# EEZ_CF-DIC_r3B3.net
KiCad netlist of a schematic drawn in EAGLE
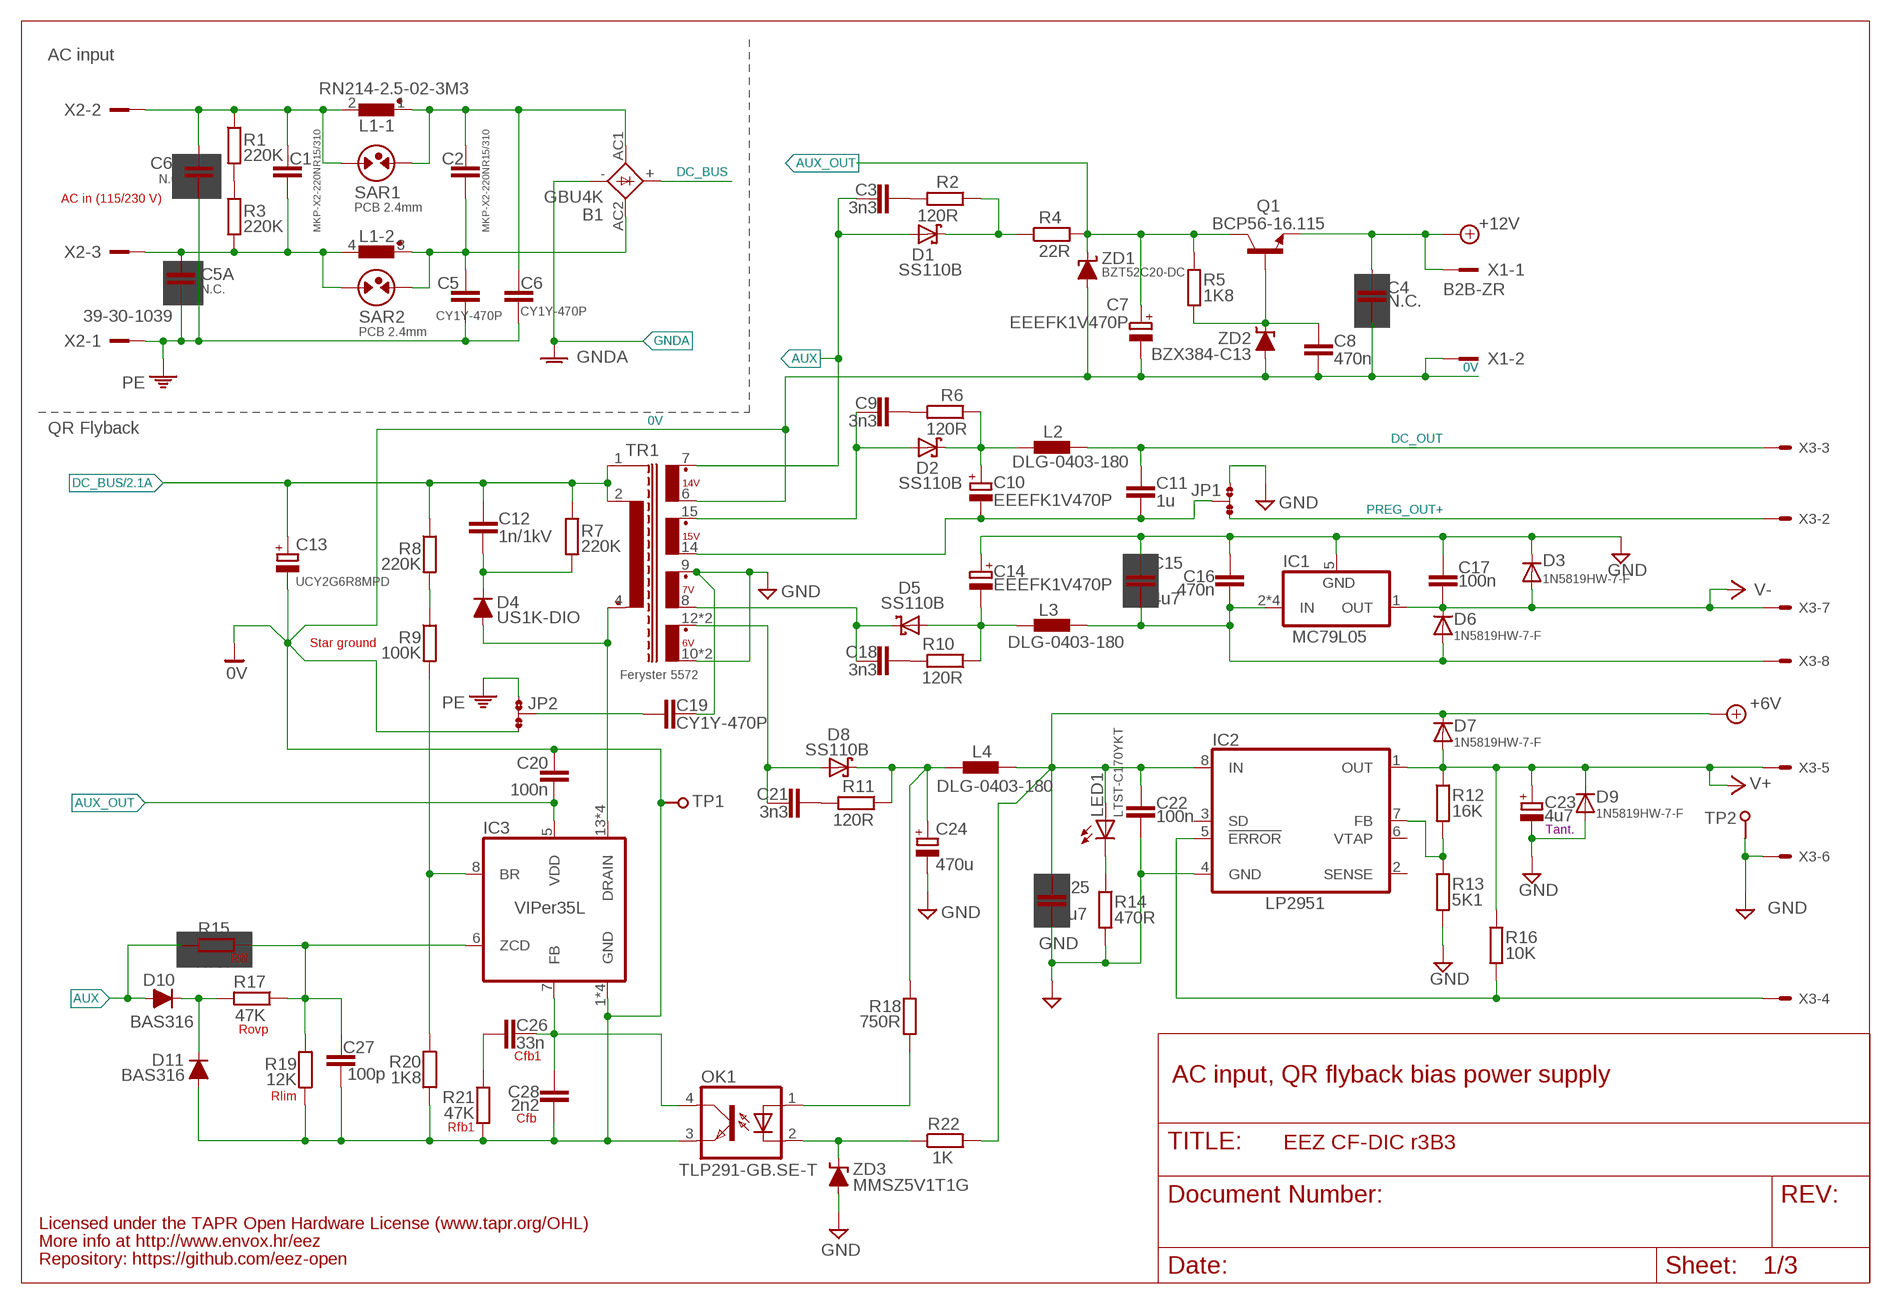
[diagram p0: schematic, sheet 1]
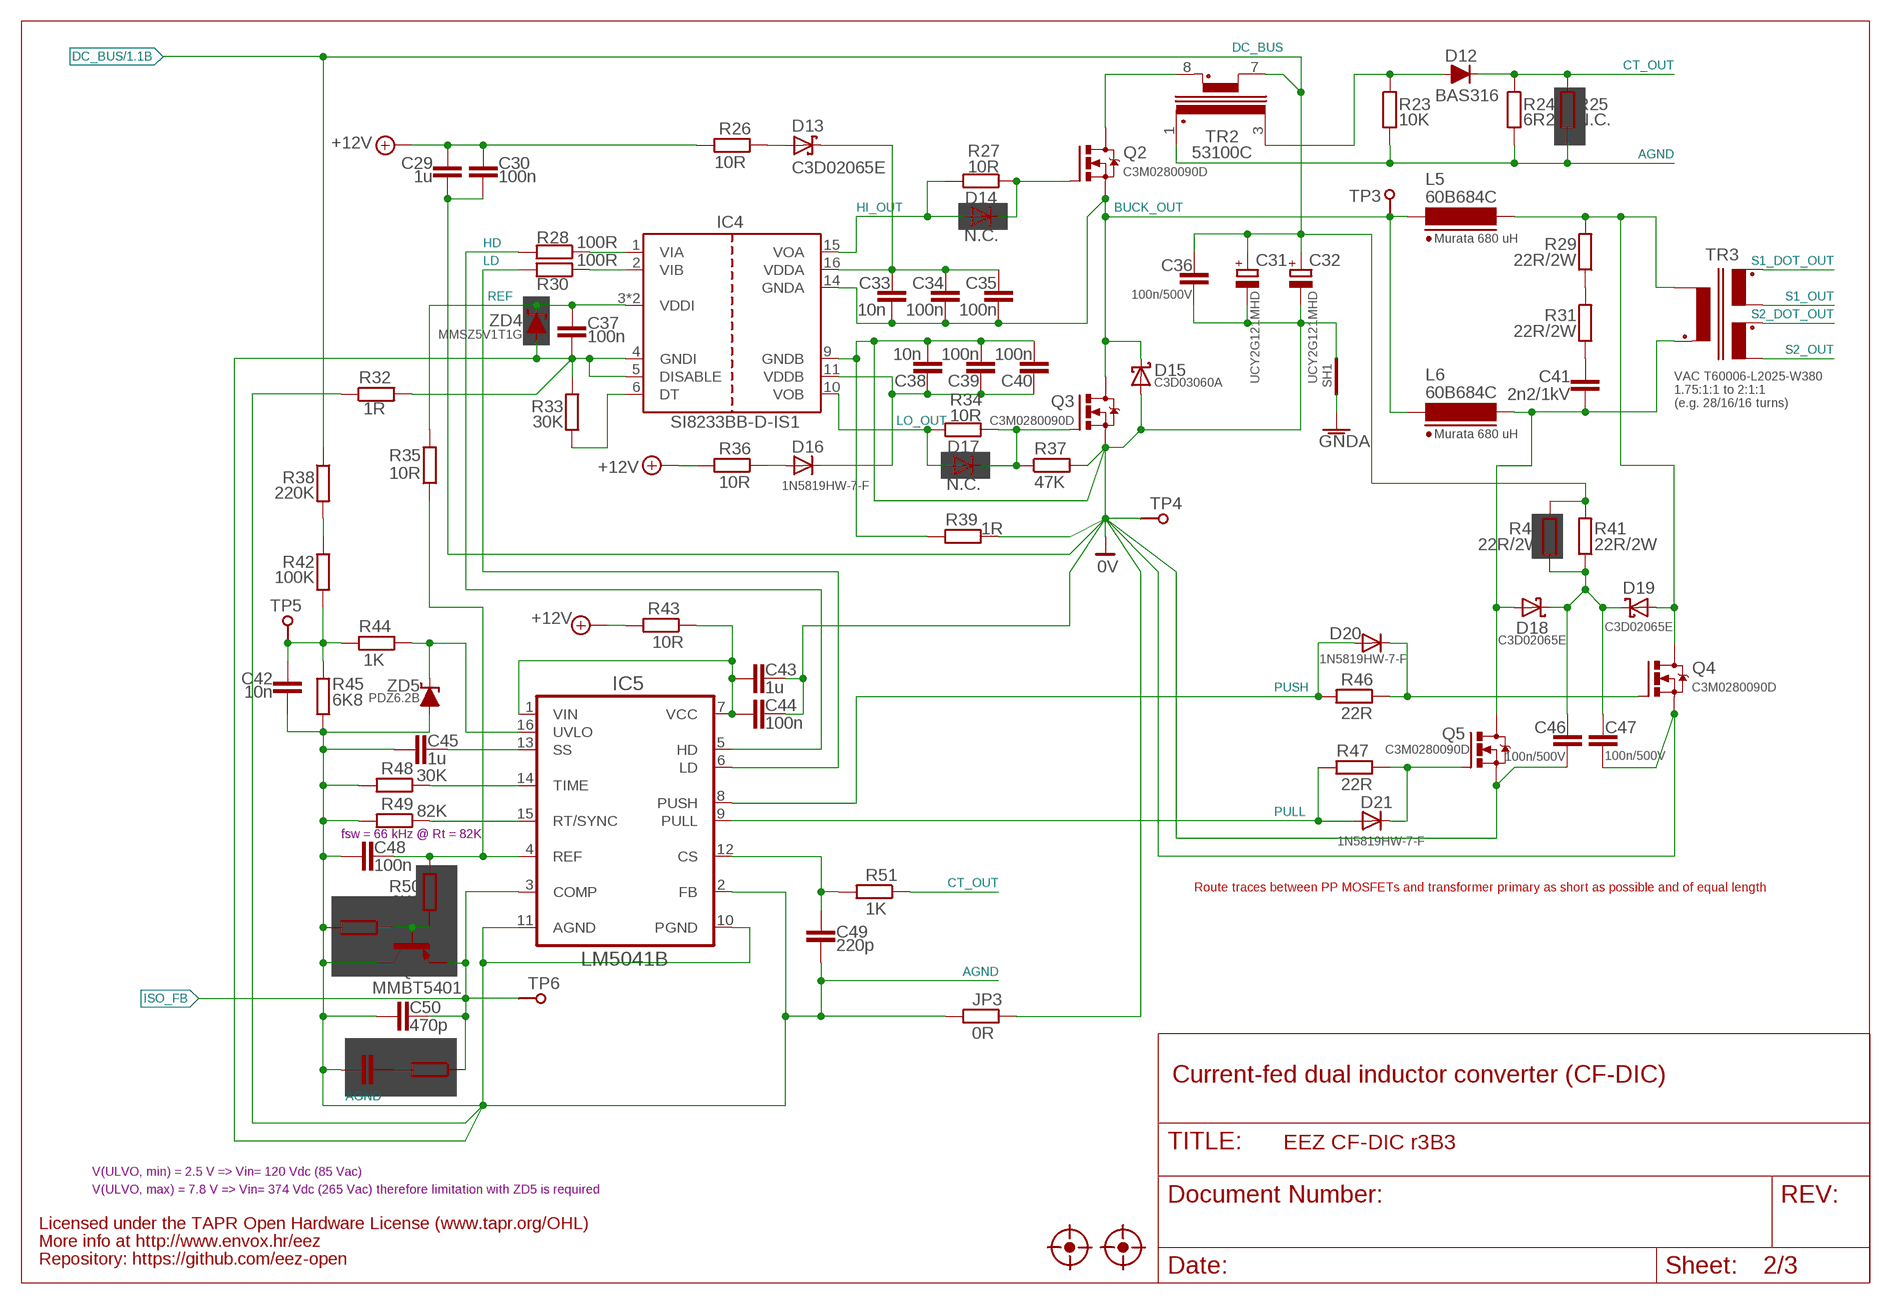
[diagram p1: schematic, sheet 2]
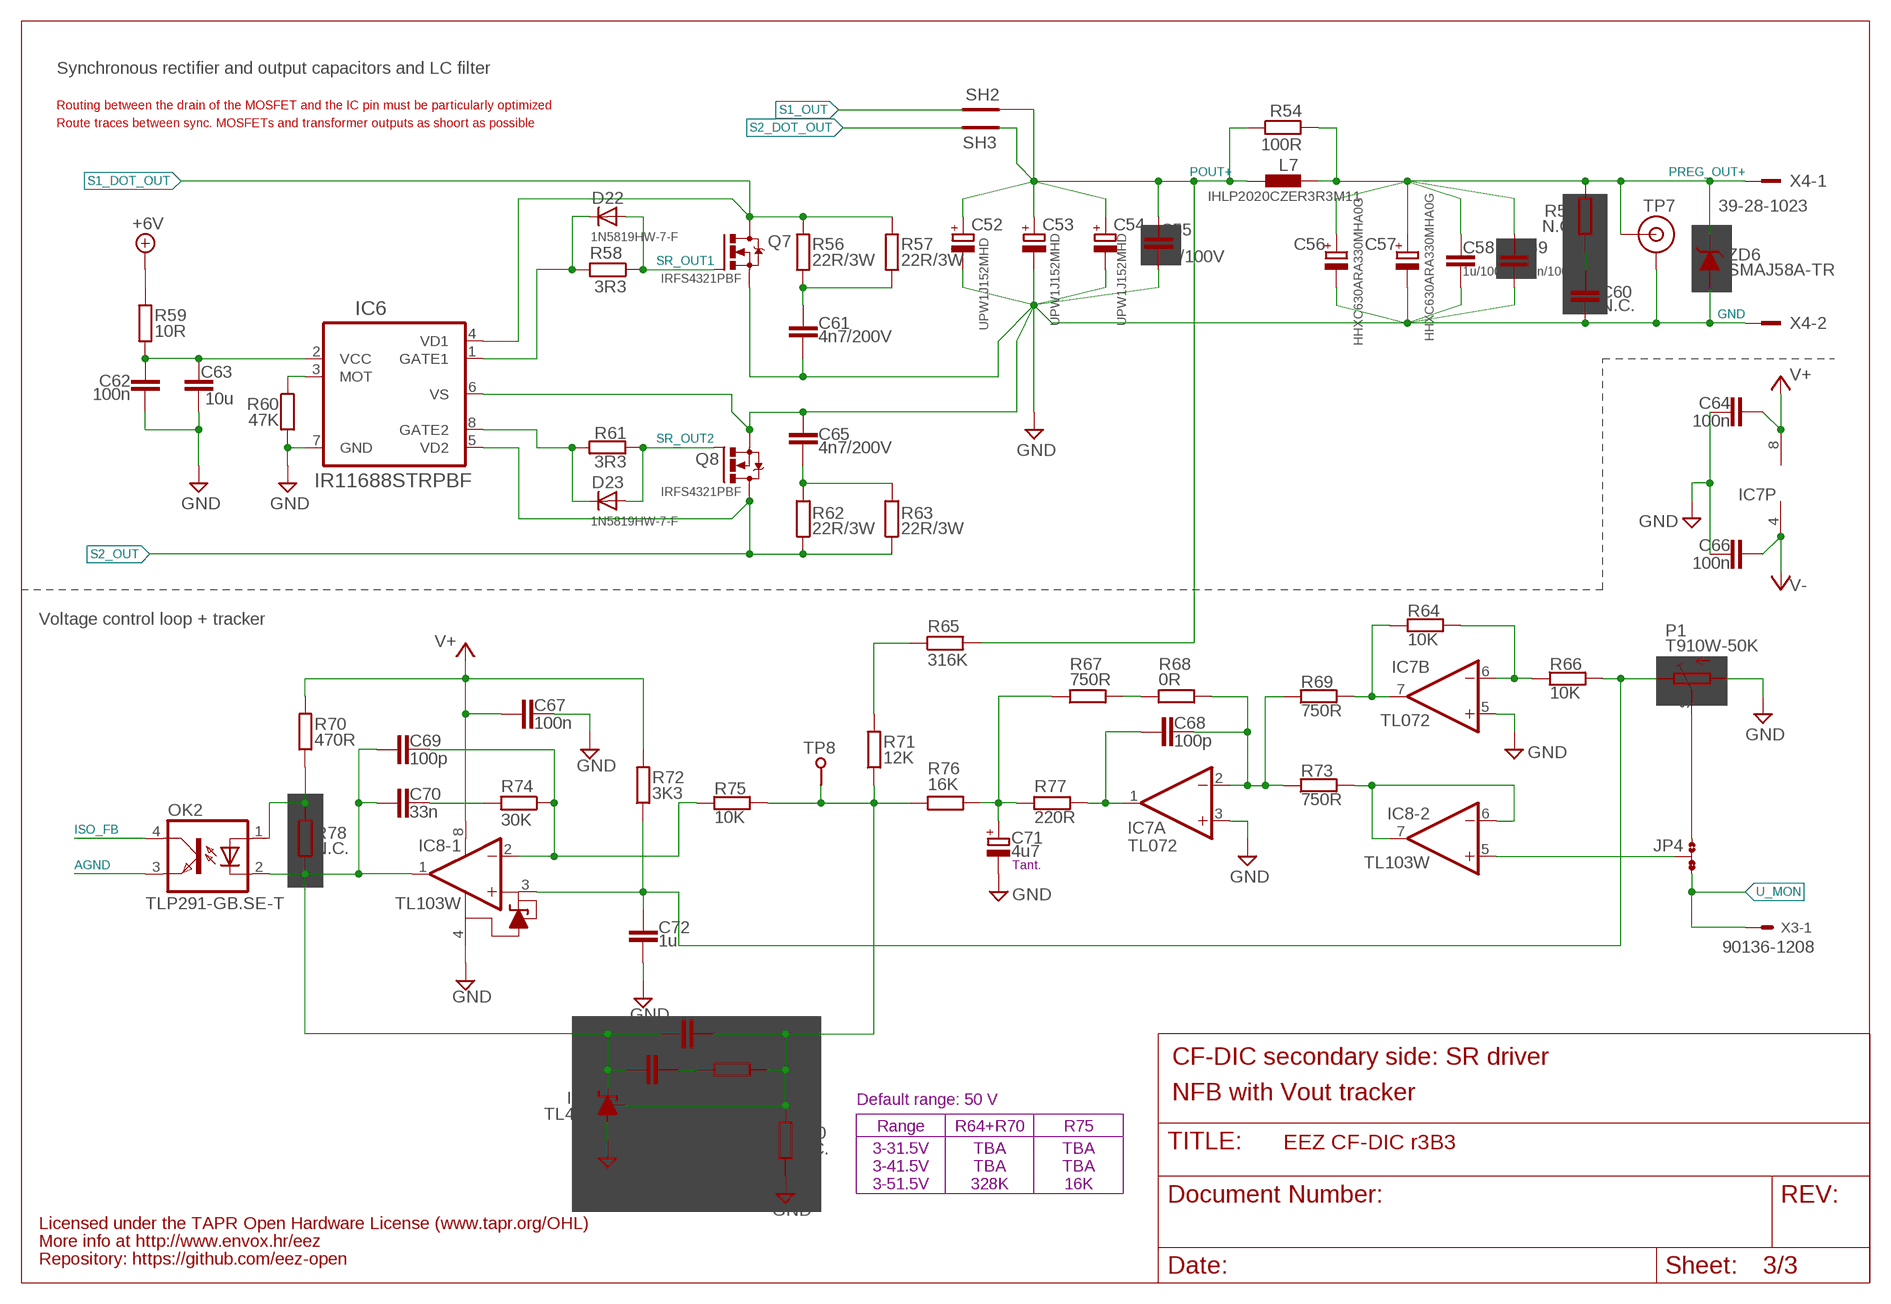
[diagram p2: schematic, sheet 3]

(export (version "E")
  (design (tool "Eeschema 10.0.6"))
  (components
    (comp (ref "C52")
      (value "UPW1J152MHD")
      (footprint "eagle-import:ECAP7.5_18")
      (libsource (lib "eagle-import") (part "ECAP7.5G_18MM"))
    )
    (comp (ref "C53")
      (value "UPW1J152MHD")
      (footprint "eagle-import:ECAP7.5_18")
      (libsource (lib "eagle-import") (part "ECAP7.5G_18MM"))
    )
    (comp (ref "C54")
      (value "UPW1J152MHD")
      (footprint "eagle-import:ECAP7.5_18")
      (libsource (lib "eagle-import") (part "ECAP7.5G_18MM"))
    )
    (comp (ref "C55")
      (value "1u/100V")
      (footprint "eagle-import:C1206")
      (libsource (lib "eagle-import") (part "C-EUC1206"))
    )
    (comp (ref "C56")
      (value "HHXC630ARA330MHA0G ")
      (footprint "eagle-import:CAPAE830X1050N")
      (fields
        (field (name "MPN") "EEE-FK1J470P")
        (field (name "TOLERANCE") "±20 %")
        (field (name "MPN_1") "EEE-FK1J470P")
        (field (name "OC_FARNELL") "9696032  ")
        (field (name "OC_NEWARK") "96K9403")
        (field (name "PACKAGE") "CASE-F")
        (field (name "SUPPLIER") "PANASONIC")
        (field (name "TOLERANCE_1") "±20 %")
        (field (name "VOLTAGERATING") "63 V")
      )
      (libsource (lib "eagle-import") (part "EEE--CASE-FFK1J470P"))
    )
    (comp (ref "C57")
      (value "HHXC630ARA330MHA0G")
      (footprint "eagle-import:CAPAE830X1050N")
      (fields (field (name "MPN") "EEE-FK1J470P") (field (name "TOLERANCE") "±20 %"))
      (libsource (lib "eagle-import") (part "EEE--CASE-FFK1J470P"))
    )
    (comp (ref "C58")
      (value "1u/100V")
      (footprint "eagle-import:C1206")
      (libsource (lib "eagle-import") (part "C-EUC1206"))
    )
    (comp (ref "C59")
      (value "100n/100V")
      (footprint "eagle-import:C0805")
      (libsource (lib "eagle-import") (part "C-EUC0805"))
    )
    (comp (ref "C60")
      (value "N.C.")
      (footprint "eagle-import:C1206")
      (libsource (lib "eagle-import") (part "C-EUC1206"))
    )
    (comp (ref "C61")
      (value "4n7/200V")
      (footprint "eagle-import:C1206")
      (libsource (lib "eagle-import") (part "C-EUC1206"))
    )
    (comp (ref "C62")
      (value "100n")
      (footprint "eagle-import:C0603")
      (libsource (lib "eagle-import") (part "C-EUC0603"))
    )
    (comp (ref "C63")
      (value "10u")
      (footprint "eagle-import:C1210")
      (libsource (lib "eagle-import") (part "C-EUC1210"))
    )
    (comp (ref "C64")
      (value "100n")
      (footprint "eagle-import:C0603")
      (libsource (lib "eagle-import") (part "C-EUC0603"))
    )
    (comp (ref "C65")
      (value "4n7/200V")
      (footprint "eagle-import:C1206")
      (libsource (lib "eagle-import") (part "C-EUC1206"))
    )
    (comp (ref "C66")
      (value "100n")
      (footprint "eagle-import:C0603")
      (libsource (lib "eagle-import") (part "C-EUC0603"))
    )
    (comp (ref "C67")
      (value "100n")
      (footprint "eagle-import:C0603")
      (libsource (lib "eagle-import") (part "C-EUC0603"))
    )
    (comp (ref "C68")
      (value "100p")
      (footprint "eagle-import:C0805")
      (libsource (lib "eagle-import") (part "C-EUC0805"))
    )
    (comp (ref "C69")
      (value "100p")
      (footprint "eagle-import:C0805")
      (libsource (lib "eagle-import") (part "C-EUC0805"))
    )
    (comp (ref "C70")
      (value "33n")
      (footprint "eagle-import:C0805")
      (libsource (lib "eagle-import") (part "C-EUC0805"))
    )
    (comp (ref "C71")
      (value "4u7")
      (footprint "eagle-import:EC1206")
      (libsource (lib "eagle-import") (part "ECAP1206"))
    )
    (comp (ref "C72")
      (value "1u")
      (footprint "eagle-import:C0805")
      (libsource (lib "eagle-import") (part "C-EUC0805"))
    )
    (comp (ref "C73")
      (value "N.C.")
      (footprint "eagle-import:C0805")
      (libsource (lib "eagle-import") (part "C-EUC0805"))
    )
    (comp (ref "C74")
      (value "N.C.")
      (footprint "eagle-import:C0805")
      (libsource (lib "eagle-import") (part "C-EUC0805"))
    )
    (comp (ref "D22")
      (value "1N5819HW-7-F")
      (footprint "eagle-import:SOD323-W")
      (libsource (lib "eagle-import") (part "DIODE-SOD323-W"))
    )
    (comp (ref "D23")
      (value "1N5819HW-7-F")
      (footprint "eagle-import:SOD323-W")
      (libsource (lib "eagle-import") (part "DIODE-SOD323-W"))
    )
    (comp (ref "IC6")
      (value "IR11688STRPBF")
      (footprint "eagle-import:SO8")
      (libsource (lib "eagle-import") (part "IR11688"))
    )
    (comp (ref "IC7")
      (value "TL072")
      (footprint "eagle-import:SOIC127P600X173-8N")
      (libsource (lib "eagle-import") (part "TL072SOIC8"))
    )
    (comp (ref "IC8")
      (value "TL103W")
      (footprint "eagle-import:SOIC127P600X173-8N")
      (libsource (lib "eagle-import") (part "TL103W"))
    )
    (comp (ref "IC9")
      (value "TL431")
      (footprint "eagle-import:SOT103P240X110-3N")
      (libsource (lib "eagle-import") (part "TL431"))
    )
    (comp (ref "JP4")
      (value "JP3-CUT")
      (footprint "eagle-import:JP3-CUT")
      (libsource (lib "eagle-import") (part "JP3-CUT"))
    )
    (comp (ref "L7")
      (value "IHLP2020CZER3R3M11")
      (footprint "eagle-import:IHLP-2020BZ-11")
      (libsource (lib "eagle-import") (part "EEZ_inductors_and_transformers_IHLP-2020BZ-11"))
    )
    (comp (ref "OK2")
      (value "TLP291-GB.SE-T")
      (footprint "eagle-import:SO4")
      (libsource (lib "eagle-import") (part "TLP291"))
    )
    (comp (ref "P1")
      (value "T910W-50K")
      (footprint "eagle-import:S64W")
      (libsource (lib "eagle-import") (part "TRIM_EU-S64W"))
    )
    (comp (ref "Q7")
      (value "IRFS4321PBF")
      (footprint "eagle-import:TO263")
      (libsource (lib "eagle-import") (part "N-MOSFETTO263"))
    )
    (comp (ref "Q8")
      (value "IRFS4321PBF")
      (footprint "eagle-import:TO263")
      (libsource (lib "eagle-import") (part "N-MOSFETTO263"))
    )
    (comp (ref "R54")
      (value "100R")
      (footprint "eagle-import:R0805")
      (libsource (lib "eagle-import") (part "R-EU_R0805"))
    )
    (comp (ref "R55")
      (value "N.C.")
      (footprint "eagle-import:R1210")
      (libsource (lib "eagle-import") (part "R-EU_R1210"))
    )
    (comp (ref "R56")
      (value "22R/3W")
      (footprint "eagle-import:R2512")
      (libsource (lib "eagle-import") (part "R-EU_R2512"))
    )
    (comp (ref "R57")
      (value "22R/3W")
      (footprint "eagle-import:R2512")
      (libsource (lib "eagle-import") (part "R-EU_R2512"))
    )
    (comp (ref "R58")
      (value "3R3")
      (footprint "eagle-import:R0805")
      (libsource (lib "eagle-import") (part "R-EU_R0805"))
    )
    (comp (ref "R59")
      (value "10R")
      (footprint "eagle-import:R0805")
      (libsource (lib "eagle-import") (part "R-EU_R0805"))
    )
    (comp (ref "R60")
      (value "47K")
      (footprint "eagle-import:R0805")
      (libsource (lib "eagle-import") (part "R-EU_R0805"))
    )
    (comp (ref "R61")
      (value "3R3")
      (footprint "eagle-import:R0805")
      (libsource (lib "eagle-import") (part "R-EU_R0805"))
    )
    (comp (ref "R62")
      (value "22R/3W")
      (footprint "eagle-import:R2512")
      (libsource (lib "eagle-import") (part "R-EU_R2512"))
    )
    (comp (ref "R63")
      (value "22R/3W")
      (footprint "eagle-import:R2512")
      (libsource (lib "eagle-import") (part "R-EU_R2512"))
    )
    (comp (ref "R64")
      (value "10K")
      (footprint "eagle-import:R0805")
      (libsource (lib "eagle-import") (part "R-EU_R0805"))
    )
    (comp (ref "R65")
      (value "316K")
      (footprint "eagle-import:R0805")
      (libsource (lib "eagle-import") (part "R-EU_R0805"))
    )
    (comp (ref "R66")
      (value "10K")
      (footprint "eagle-import:R0805")
      (libsource (lib "eagle-import") (part "R-EU_R0805"))
    )
    (comp (ref "R67")
      (value "750R")
      (footprint "eagle-import:R0805")
      (libsource (lib "eagle-import") (part "R-EU_R0805"))
    )
    (comp (ref "R68")
      (value "0R")
      (footprint "eagle-import:R0805")
      (libsource (lib "eagle-import") (part "R-EU_R0805"))
    )
    (comp (ref "R69")
      (value "750R")
      (footprint "eagle-import:R0805")
      (libsource (lib "eagle-import") (part "R-EU_R0805"))
    )
    (comp (ref "R70")
      (value "470R")
      (footprint "eagle-import:R0805")
      (libsource (lib "eagle-import") (part "R-EU_R0805"))
    )
    (comp (ref "R71")
      (value "12K")
      (footprint "eagle-import:R0805")
      (libsource (lib "eagle-import") (part "R-EU_R0805"))
    )
    (comp (ref "R72")
      (value "3K3")
      (footprint "eagle-import:R0805")
      (libsource (lib "eagle-import") (part "R-EU_R0805"))
    )
    (comp (ref "R73")
      (value "750R")
      (footprint "eagle-import:R0805")
      (libsource (lib "eagle-import") (part "R-EU_R0805"))
    )
    (comp (ref "R74")
      (value "30K")
      (footprint "eagle-import:R0805")
      (libsource (lib "eagle-import") (part "R-EU_R0805"))
    )
    (comp (ref "R75")
      (value "10K")
      (footprint "eagle-import:R0805")
      (libsource (lib "eagle-import") (part "R-EU_R0805"))
    )
    (comp (ref "R76")
      (value "16K")
      (footprint "eagle-import:R0805")
      (libsource (lib "eagle-import") (part "R-EU_R0805"))
    )
    (comp (ref "R77")
      (value "220R")
      (footprint "eagle-import:R0805")
      (libsource (lib "eagle-import") (part "R-EU_R0805"))
    )
    (comp (ref "R78")
      (value "N.C.")
      (footprint "eagle-import:R0805")
      (libsource (lib "eagle-import") (part "R-EU_R0805"))
    )
    (comp (ref "R79")
      (value "N.C.")
      (footprint "eagle-import:R0805")
      (libsource (lib "eagle-import") (part "R-EU_R0805"))
    )
    (comp (ref "R80")
      (value "N.C.")
      (footprint "eagle-import:R0805")
      (libsource (lib "eagle-import") (part "R-EU_R0805"))
    )
    (comp (ref "SH2")
      (value "SHORTNOHOLE")
      (footprint "eagle-import:SHORT_NOHOLE")
      (libsource (lib "eagle-import") (part "SHORTNOHOLE"))
    )
    (comp (ref "SH3")
      (value "SHORTNOHOLE")
      (footprint "eagle-import:SHORT_NOHOLE")
      (libsource (lib "eagle-import") (part "SHORTNOHOLE"))
    )
    (comp (ref "TP7")
      (value "TEST_POINT-2")
      (footprint "eagle-import:TP_1.1MM_2")
      (libsource (lib "eagle-import") (part "TEST_POINT-2"))
    )
    (comp (ref "TP8")
      (value "PCB_TEST_TABSHIELD")
      (footprint "eagle-import:PCB_SHIELD_TAB")
      (libsource (lib "eagle-import") (part "PCB_TEST_TABSHIELD"))
    )
    (comp (ref "X3")
      (value "90136-1208")
      (footprint "eagle-import:70543-08")
      (libsource (lib "eagle-import") (part "C-GRID-08-70543"))
    )
    (comp (ref "X4")
      (value "39-28-1023")
      (footprint "eagle-import:MINIFIT_5566-02A")
      (libsource (lib "eagle-import") (part "MINIFIT_5566-02A"))
    )
    (comp (ref "ZD6")
      (value "SMAJ58A-TR")
      (footprint "eagle-import:DO214AC")
      (libsource (lib "eagle-import") (part "PSMAXX"))
    )
    (comp (ref "B1")
      (value "GBU4K")
      (footprint "eagle-import:GBU4K_CRE")
      (libsource (lib "eagle-import") (part "BRIDGE-CREEPAGE"))
    )
    (comp (ref "C1")
      (value "MKP-X2-220NR15/310")
      (footprint "eagle-import:C150-072X183")
      (libsource (lib "eagle-import") (part "C-EU150-072X183"))
    )
    (comp (ref "C2")
      (value "MKP-X2-220NR15/310")
      (footprint "eagle-import:C150-072X183")
      (libsource (lib "eagle-import") (part "C-EU150-072X183"))
    )
    (comp (ref "C3")
      (value "3n3")
      (footprint "eagle-import:C0805")
      (libsource (lib "eagle-import") (part "C-EUC0805"))
    )
    (comp (ref "C4")
      (value "N.C.")
      (footprint "eagle-import:C0603")
      (libsource (lib "eagle-import") (part "C-EUC0603"))
    )
    (comp (ref "C5")
      (value "CY1Y-470P")
      (footprint "eagle-import:CY075-032X103")
      (libsource (lib "eagle-import") (part "C-EUCY"))
    )
    (comp (ref "C5A")
      (value "N.C.")
      (footprint "eagle-import:CY075-032X103")
      (libsource (lib "eagle-import") (part "C-EUCY"))
    )
    (comp (ref "C6")
      (value "CY1Y-470P")
      (footprint "eagle-import:CY075-032X103")
      (libsource (lib "eagle-import") (part "C-EUCY"))
    )
    (comp (ref "C6A")
      (value "N.C.")
      (footprint "eagle-import:CY075-032X103")
      (libsource (lib "eagle-import") (part "C-EUCY"))
    )
    (comp (ref "C7")
      (value "EEEFK1V470P")
      (footprint "eagle-import:CAPAE660X610N")
      (libsource (lib "eagle-import") (part "ECAPPANASONIC_H"))
    )
    (comp (ref "C8")
      (value "470n")
      (footprint "eagle-import:C0805")
      (libsource (lib "eagle-import") (part "C-EUC0805"))
    )
    (comp (ref "C9")
      (value "3n3")
      (footprint "eagle-import:C0805")
      (libsource (lib "eagle-import") (part "C-EUC0805"))
    )
    (comp (ref "C10")
      (value "EEEFK1V470P")
      (footprint "eagle-import:CAPAE660X610N")
      (libsource (lib "eagle-import") (part "ECAPPANASONIC_H"))
    )
    (comp (ref "C11")
      (value "1u")
      (footprint "eagle-import:C0805")
      (libsource (lib "eagle-import") (part "C-EUC0805"))
    )
    (comp (ref "C12")
      (value "1n/1kV")
      (footprint "eagle-import:C1210")
      (libsource (lib "eagle-import") (part "C-EUC1210"))
    )
    (comp (ref "C13")
      (value "UCY2G6R8MPD")
      (footprint "eagle-import:ECAP5_10.5")
      (libsource (lib "eagle-import") (part "ECAP5G_10.5MM"))
    )
    (comp (ref "C14")
      (value "EEEFK1V470P")
      (footprint "eagle-import:CAPAE660X610N")
      (libsource (lib "eagle-import") (part "ECAPPANASONIC_H"))
    )
    (comp (ref "C15")
      (value "4u7")
      (footprint "eagle-import:C1206")
      (libsource (lib "eagle-import") (part "C-EUC1206"))
    )
    (comp (ref "C16")
      (value "470n")
      (footprint "eagle-import:C0805")
      (libsource (lib "eagle-import") (part "C-EUC0805"))
    )
    (comp (ref "C17")
      (value "100n")
      (footprint "eagle-import:C0603")
      (libsource (lib "eagle-import") (part "C-EUC0603"))
    )
    (comp (ref "C18")
      (value "3n3")
      (footprint "eagle-import:C0805")
      (libsource (lib "eagle-import") (part "C-EUC0805"))
    )
    (comp (ref "C19")
      (value "CY1Y-470P")
      (footprint "eagle-import:CY075-032X103")
      (libsource (lib "eagle-import") (part "C-EUCY"))
    )
    (comp (ref "C20")
      (value "100n")
      (footprint "eagle-import:C0603")
      (libsource (lib "eagle-import") (part "C-EUC0603"))
    )
    (comp (ref "C21")
      (value "3n3")
      (footprint "eagle-import:C0805")
      (libsource (lib "eagle-import") (part "C-EUC0805"))
    )
    (comp (ref "C22")
      (value "100n")
      (footprint "eagle-import:C0603")
      (libsource (lib "eagle-import") (part "C-EUC0603"))
    )
    (comp (ref "C23")
      (value "4u7")
      (footprint "eagle-import:EC1206")
      (libsource (lib "eagle-import") (part "ECAP1206"))
    )
    (comp (ref "C24")
      (value "470u")
      (footprint "eagle-import:ECAP5_10.5")
      (libsource (lib "eagle-import") (part "ECAP5G_10.5MM"))
    )
    (comp (ref "C25")
      (value "4u7")
      (footprint "eagle-import:C1206")
      (libsource (lib "eagle-import") (part "C-EUC1206"))
    )
    (comp (ref "C26")
      (value "33n")
      (footprint "eagle-import:C0805")
      (libsource (lib "eagle-import") (part "C-EUC0805"))
    )
    (comp (ref "C27")
      (value "100p")
      (footprint "eagle-import:C0805")
      (libsource (lib "eagle-import") (part "C-EUC0805"))
    )
    (comp (ref "C28")
      (value "2n2")
      (footprint "eagle-import:C0805")
      (libsource (lib "eagle-import") (part "C-EUC0805"))
    )
    (comp (ref "D1")
      (value "SS110B")
      (footprint "eagle-import:SMB")
      (libsource (lib "eagle-import") (part "SCHOTTKYSMB"))
    )
    (comp (ref "D2")
      (value "SS110B")
      (footprint "eagle-import:SMB")
      (libsource (lib "eagle-import") (part "SCHOTTKYSMB"))
    )
    (comp (ref "D3")
      (value "1N5819HW-7-F")
      (footprint "eagle-import:SOD323-W")
      (libsource (lib "eagle-import") (part "DIODE-SOD323-W"))
    )
    (comp (ref "D4")
      (value "US1K-DIO")
      (footprint "eagle-import:DO214AA")
      (libsource (lib "eagle-import") (part "DIODEDO214AA"))
    )
    (comp (ref "D5")
      (value "SS110B")
      (footprint "eagle-import:SMB")
      (libsource (lib "eagle-import") (part "SCHOTTKYSMB"))
    )
    (comp (ref "D6")
      (value "1N5819HW-7-F")
      (footprint "eagle-import:SOD323-W")
      (libsource (lib "eagle-import") (part "DIODE-SOD323-W"))
    )
    (comp (ref "D7")
      (value "1N5819HW-7-F")
      (footprint "eagle-import:SOD323-W")
      (libsource (lib "eagle-import") (part "DIODE-SOD323-W"))
    )
    (comp (ref "D8")
      (value "SS110B")
      (footprint "eagle-import:SMB")
      (libsource (lib "eagle-import") (part "SCHOTTKYSMB"))
    )
    (comp (ref "D9")
      (value "1N5819HW-7-F")
      (footprint "eagle-import:SOD323-W")
      (libsource (lib "eagle-import") (part "DIODE-SOD323-W"))
    )
    (comp (ref "D10")
      (value "BAS316")
      (footprint "eagle-import:SOD323-R")
      (libsource (lib "eagle-import") (part "DIODESOD323R"))
    )
    (comp (ref "D11")
      (value "BAS316")
      (footprint "eagle-import:SOD323-R")
      (libsource (lib "eagle-import") (part "DIODESOD323R"))
    )
    (comp (ref "IC1")
      (value "MC79L05")
      (footprint "eagle-import:SOIC127P600X173-8N")
      (libsource (lib "eagle-import") (part "MC79LXXSOIC"))
    )
    (comp (ref "IC2")
      (value "LP2951")
      (footprint "eagle-import:SOIC127P600X175-8N")
      (libsource (lib "eagle-import") (part "LP2951SO8"))
    )
    (comp (ref "IC3")
      (value "VIPer35L")
      (footprint "eagle-import:SOIC-16")
      (libsource (lib "eagle-import") (part "VIPER35"))
    )
    (comp (ref "JP1")
      (value "JP3-CUT")
      (footprint "eagle-import:JP3-CUT")
      (libsource (lib "eagle-import") (part "JP3-CUT"))
    )
    (comp (ref "JP2")
      (value "JP3-CUT")
      (footprint "eagle-import:JP3-CUT")
      (libsource (lib "eagle-import") (part "JP3-CUT"))
    )
    (comp (ref "L1")
      (value "RN214-2.5-02-3M3")
      (footprint "eagle-import:RN214")
      (fields (field (name "FARNELL") "1191518"))
      (libsource (lib "eagle-import") (part "EEZ_inductors_and_transformers_RN214"))
    )
    (comp (ref "L2")
      (value "DLG-0403-180")
      (footprint "eagle-import:DE0403")
      (libsource (lib "eagle-import") (part "EEZ_inductors_and_transformers_DE0403"))
    )
    (comp (ref "L3")
      (value "DLG-0403-180")
      (footprint "eagle-import:DE0403")
      (libsource (lib "eagle-import") (part "EEZ_inductors_and_transformers_DE0403"))
    )
    (comp (ref "L4")
      (value "DLG-0403-180")
      (footprint "eagle-import:DE0403")
      (libsource (lib "eagle-import") (part "EEZ_inductors_and_transformers_DE0403"))
    )
    (comp (ref "LED1")
      (value "LTST-C170YKT")
      (footprint "eagle-import:LED_0805")
      (libsource (lib "eagle-import") (part "LED0805"))
    )
    (comp (ref "OK1")
      (value "TLP291-GB.SE-T")
      (footprint "eagle-import:SO4")
      (libsource (lib "eagle-import") (part "TLP291"))
    )
    (comp (ref "Q1")
      (value "BCP56-16.115")
      (footprint "eagle-import:SOT230P700X180-4N")
      (libsource (lib "eagle-import") (part "BCP56"))
    )
    (comp (ref "R1")
      (value "220K")
      (footprint "eagle-import:R1206")
      (libsource (lib "eagle-import") (part "R-EU_R1206"))
    )
    (comp (ref "R2")
      (value "120R")
      (footprint "eagle-import:R0805")
      (libsource (lib "eagle-import") (part "R-EU_R0805"))
    )
    (comp (ref "R3")
      (value "220K")
      (footprint "eagle-import:R1206")
      (libsource (lib "eagle-import") (part "R-EU_R1206"))
    )
    (comp (ref "R4")
      (value "22R")
      (footprint "eagle-import:R0805")
      (libsource (lib "eagle-import") (part "R-EU_R0805"))
    )
    (comp (ref "R5")
      (value "1K8")
      (footprint "eagle-import:R0805")
      (libsource (lib "eagle-import") (part "R-EU_R0805"))
    )
    (comp (ref "R6")
      (value "120R")
      (footprint "eagle-import:R0805")
      (libsource (lib "eagle-import") (part "R-EU_R0805"))
    )
    (comp (ref "R7")
      (value "220K")
      (footprint "eagle-import:R1206")
      (libsource (lib "eagle-import") (part "R-EU_R1206"))
    )
    (comp (ref "R8")
      (value "220K")
      (footprint "eagle-import:R1206")
      (libsource (lib "eagle-import") (part "R-EU_R1206"))
    )
    (comp (ref "R9")
      (value "100K")
      (footprint "eagle-import:R0805")
      (libsource (lib "eagle-import") (part "R-EU_R0805"))
    )
    (comp (ref "R10")
      (value "120R")
      (footprint "eagle-import:R0805")
      (libsource (lib "eagle-import") (part "R-EU_R0805"))
    )
    (comp (ref "R11")
      (value "120R")
      (footprint "eagle-import:R0805")
      (libsource (lib "eagle-import") (part "R-EU_R0805"))
    )
    (comp (ref "R12")
      (value "16K")
      (footprint "eagle-import:R0805")
      (libsource (lib "eagle-import") (part "R-EU_R0805"))
    )
    (comp (ref "R13")
      (value "5K1")
      (footprint "eagle-import:R0805")
      (libsource (lib "eagle-import") (part "R-EU_R0805"))
    )
    (comp (ref "R14")
      (value "470R")
      (footprint "eagle-import:R0805")
      (libsource (lib "eagle-import") (part "R-EU_R0805"))
    )
    (comp (ref "R15")
      (value "N.C.")
      (footprint "eagle-import:R0805")
      (libsource (lib "eagle-import") (part "R-EU_R0805"))
    )
    (comp (ref "R16")
      (value "10K")
      (footprint "eagle-import:R0805")
      (libsource (lib "eagle-import") (part "R-EU_R0805"))
    )
    (comp (ref "R17")
      (value "47K")
      (footprint "eagle-import:R0805")
      (libsource (lib "eagle-import") (part "R-EU_R0805"))
    )
    (comp (ref "R18")
      (value "750R")
      (footprint "eagle-import:R0805")
      (libsource (lib "eagle-import") (part "R-EU_R0805"))
    )
    (comp (ref "R19")
      (value "12K")
      (footprint "eagle-import:R0805")
      (libsource (lib "eagle-import") (part "R-EU_R0805"))
    )
    (comp (ref "R20")
      (value "1K8")
      (footprint "eagle-import:R0805")
      (libsource (lib "eagle-import") (part "R-EU_R0805"))
    )
    (comp (ref "R21")
      (value "47K")
      (footprint "eagle-import:R0805")
      (libsource (lib "eagle-import") (part "R-EU_R0805"))
    )
    (comp (ref "R22")
      (value "1K")
      (footprint "eagle-import:R0805")
      (libsource (lib "eagle-import") (part "R-EU_R0805"))
    )
    (comp (ref "SAR1")
      (value "PCB 2.4mm")
      (footprint "eagle-import:PCB-SAR_2.4MM")
      (libsource (lib "eagle-import") (part "SARPCB-2.4MM"))
    )
    (comp (ref "SAR2")
      (value "PCB 2.4mm")
      (footprint "eagle-import:PCB-SAR_2.4MM")
      (libsource (lib "eagle-import") (part "SARPCB-2.4MM"))
    )
    (comp (ref "TP1")
      (value "PCB_TEST_TABSHIELD")
      (footprint "eagle-import:PCB_SHIELD_TAB")
      (libsource (lib "eagle-import") (part "PCB_TEST_TABSHIELD"))
    )
    (comp (ref "TP2")
      (value "PCB_TEST_TABSHIELD")
      (footprint "eagle-import:PCB_SHIELD_TAB")
      (libsource (lib "eagle-import") (part "PCB_TEST_TABSHIELD"))
    )
    (comp (ref "TR1")
      (value "Feryster 5572")
      (footprint "eagle-import:FERYSTER_5572")
      (libsource (lib "eagle-import") (part "EEZ_inductors_and_transformers_FERYSTER_5572"))
    )
    (comp (ref "X1")
      (value "B2B-ZR")
      (footprint "eagle-import:B2B-ZR")
      (libsource (lib "eagle-import") (part "B2B-ZR"))
    )
    (comp (ref "X2")
      (value "39-30-1039")
      (footprint "eagle-import:MINIFIT_39301039_CRE")
      (libsource (lib "eagle-import") (part "MINIFIT_39301039-CREEPAGE"))
    )
    (comp (ref "ZD1")
      (value "BZT52C20-DC")
      (footprint "eagle-import:SOD123FL")
      (libsource (lib "eagle-import") (part "ZENER-DIODESOD123FL"))
    )
    (comp (ref "ZD2")
      (value "BZX384-C13")
      (footprint "eagle-import:SOD323-W")
      (libsource (lib "eagle-import") (part "ZENER-DIODESOD323"))
    )
    (comp (ref "ZD3")
      (value "MMSZ5V1T1G")
      (footprint "eagle-import:SOD323-W")
      (libsource (lib "eagle-import") (part "ZENER-DIODESOD323"))
    )
    (comp (ref "C29")
      (value "1u")
      (footprint "eagle-import:C0805")
      (libsource (lib "eagle-import") (part "C-EUC0805"))
    )
    (comp (ref "C30")
      (value "100n")
      (footprint "eagle-import:C0603")
      (libsource (lib "eagle-import") (part "C-EUC0603"))
    )
    (comp (ref "C31")
      (value "UCY2G121MHD")
      (footprint "eagle-import:ECAP7.5_18")
      (libsource (lib "eagle-import") (part "ECAP7.5G_18MM"))
    )
    (comp (ref "C32")
      (value "UCY2G121MHD")
      (footprint "eagle-import:ECAP7.5_18")
      (libsource (lib "eagle-import") (part "ECAP7.5G_18MM"))
    )
    (comp (ref "C33")
      (value "10n")
      (footprint "eagle-import:C0603")
      (libsource (lib "eagle-import") (part "C-EUC0603"))
    )
    (comp (ref "C34")
      (value "100n")
      (footprint "eagle-import:C0603")
      (libsource (lib "eagle-import") (part "C-EUC0603"))
    )
    (comp (ref "C35")
      (value "100n")
      (footprint "eagle-import:C0603")
      (libsource (lib "eagle-import") (part "C-EUC0603"))
    )
    (comp (ref "C36")
      (value "100n/500V")
      (footprint "eagle-import:C1812")
      (libsource (lib "eagle-import") (part "C-EUC1812"))
    )
    (comp (ref "C37")
      (value "100n")
      (footprint "eagle-import:C0603")
      (libsource (lib "eagle-import") (part "C-EUC0603"))
    )
    (comp (ref "C38")
      (value "10n")
      (footprint "eagle-import:C0603")
      (libsource (lib "eagle-import") (part "C-EUC0603"))
    )
    (comp (ref "C39")
      (value "100n")
      (footprint "eagle-import:C0603")
      (libsource (lib "eagle-import") (part "C-EUC0603"))
    )
    (comp (ref "C40")
      (value "100n")
      (footprint "eagle-import:C0603")
      (libsource (lib "eagle-import") (part "C-EUC0603"))
    )
    (comp (ref "C41")
      (value "2n2/1kV")
      (footprint "eagle-import:C1210")
      (libsource (lib "eagle-import") (part "C-EUC1210"))
    )
    (comp (ref "C42")
      (value "10n")
      (footprint "eagle-import:C0603")
      (libsource (lib "eagle-import") (part "C-EUC0603"))
    )
    (comp (ref "C43")
      (value "1u")
      (footprint "eagle-import:C0805")
      (libsource (lib "eagle-import") (part "C-EUC0805"))
    )
    (comp (ref "C44")
      (value "100n")
      (footprint "eagle-import:C0603")
      (libsource (lib "eagle-import") (part "C-EUC0603"))
    )
    (comp (ref "C45")
      (value "1u")
      (footprint "eagle-import:C0805")
      (libsource (lib "eagle-import") (part "C-EUC0805"))
    )
    (comp (ref "C46")
      (value "100n/500V")
      (footprint "eagle-import:C1812")
      (libsource (lib "eagle-import") (part "C-EUC1812"))
    )
    (comp (ref "C47")
      (value "100n/500V")
      (footprint "eagle-import:C1812")
      (libsource (lib "eagle-import") (part "C-EUC1812"))
    )
    (comp (ref "C48")
      (value "100n")
      (footprint "eagle-import:C0603")
      (libsource (lib "eagle-import") (part "C-EUC0603"))
    )
    (comp (ref "C49")
      (value "220p")
      (footprint "eagle-import:C0805")
      (libsource (lib "eagle-import") (part "C-EUC0805"))
    )
    (comp (ref "C50")
      (value "470p")
      (footprint "eagle-import:C0805")
      (libsource (lib "eagle-import") (part "C-EUC0805"))
    )
    (comp (ref "C51")
      (value "N.C.")
      (footprint "eagle-import:C0805")
      (libsource (lib "eagle-import") (part "C-EUC0805"))
    )
    (comp (ref "D12")
      (value "BAS316")
      (footprint "eagle-import:SOD323-R")
      (libsource (lib "eagle-import") (part "DIODESOD323R"))
    )
    (comp (ref "D13")
      (value "C3D02065E")
      (footprint "eagle-import:TO252")
      (libsource (lib "eagle-import") (part "SCHOTTKY-2"))
    )
    (comp (ref "D14")
      (value "N.C.")
      (footprint "eagle-import:SOD323-W")
      (libsource (lib "eagle-import") (part "DIODE-SOD323-W"))
    )
    (comp (ref "D15")
      (value "C3D03060A")
      (footprint "eagle-import:TO220-2")
      (libsource (lib "eagle-import") (part "SCHOTTKY-TO220"))
    )
    (comp (ref "D16")
      (value "1N5819HW-7-F")
      (footprint "eagle-import:SOD323-W")
      (libsource (lib "eagle-import") (part "DIODE-SOD323-W"))
    )
    (comp (ref "D17")
      (value "N.C.")
      (footprint "eagle-import:SOD323-W")
      (libsource (lib "eagle-import") (part "DIODE-SOD323-W"))
    )
    (comp (ref "D18")
      (value "C3D02065E")
      (footprint "eagle-import:TO252")
      (libsource (lib "eagle-import") (part "SCHOTTKY-2"))
    )
    (comp (ref "D19")
      (value "C3D02065E")
      (footprint "eagle-import:TO252")
      (libsource (lib "eagle-import") (part "SCHOTTKY-2"))
    )
    (comp (ref "D20")
      (value "1N5819HW-7-F")
      (footprint "eagle-import:SOD323-W")
      (libsource (lib "eagle-import") (part "DIODE-SOD323-W"))
    )
    (comp (ref "D21")
      (value "1N5819HW-7-F")
      (footprint "eagle-import:SOD323-W")
      (libsource (lib "eagle-import") (part "DIODE-SOD323-W"))
    )
    (comp (ref "FM1")
      (value "FIDUCIAL_2")
      (footprint "eagle-import:FIDUCIAL_DUAL")
      (libsource (lib "eagle-import") (part "FIDUCIAL_2"))
    )
    (comp (ref "FM2")
      (value "FIDUCIAL_2")
      (footprint "eagle-import:FIDUCIAL_DUAL")
      (libsource (lib "eagle-import") (part "FIDUCIAL_2"))
    )
    (comp (ref "IC4")
      (value "SI8233BB-D-IS1")
      (footprint "eagle-import:SOIC-16")
      (libsource (lib "eagle-import") (part "SI8233"))
    )
    (comp (ref "IC5")
      (value "LM5041B")
      (footprint "eagle-import:MTC16")
      (fields (field (name "MANUFACTURER_PART_NUMBER") "lm5041mtcnopb"))
      (libsource (lib "eagle-import") (part "LM5041"))
    )
    (comp (ref "JP3")
      (value "0R")
      (footprint "eagle-import:R0805")
      (libsource (lib "eagle-import") (part "R-EU_R0805"))
    )
    (comp (ref "L5")
      (value "60B684C")
      (footprint "eagle-import:MURATA_6000B")
      (libsource (lib "eagle-import") (part "EEZ_inductors_and_transformers_MURATA_6000B"))
    )
    (comp (ref "L6")
      (value "60B684C")
      (footprint "eagle-import:MURATA_6000B")
      (libsource (lib "eagle-import") (part "EEZ_inductors_and_transformers_MURATA_6000B"))
    )
    (comp (ref "Q2")
      (value "C3M0280090D")
      (footprint "eagle-import:TO247BV")
      (libsource (lib "eagle-import") (part "IRFP240"))
    )
    (comp (ref "Q3")
      (value "C3M0280090D")
      (footprint "eagle-import:TO247BV")
      (libsource (lib "eagle-import") (part "IRFP240"))
    )
    (comp (ref "Q4")
      (value "C3M0280090D")
      (footprint "eagle-import:TO247BV")
      (libsource (lib "eagle-import") (part "IRFP240"))
    )
    (comp (ref "Q5")
      (value "C3M0280090D")
      (footprint "eagle-import:TO247BV")
      (libsource (lib "eagle-import") (part "IRFP240"))
    )
    (comp (ref "Q6")
      (value "MMBT5401")
      (footprint "eagle-import:SOT23-BEC")
      (libsource (lib "eagle-import") (part "-PNP-SOT23-BECBC857B"))
    )
    (comp (ref "R23")
      (value "10K")
      (footprint "eagle-import:R0805")
      (libsource (lib "eagle-import") (part "R-EU_R0805"))
    )
    (comp (ref "R24")
      (value "6R2")
      (footprint "eagle-import:R0805")
      (libsource (lib "eagle-import") (part "R-EU_R0805"))
    )
    (comp (ref "R25")
      (value "N.C.")
      (footprint "eagle-import:R0805")
      (libsource (lib "eagle-import") (part "R-EU_R0805"))
    )
    (comp (ref "R26")
      (value "10R")
      (footprint "eagle-import:R0805")
      (libsource (lib "eagle-import") (part "R-EU_R0805"))
    )
    (comp (ref "R27")
      (value "10R")
      (footprint "eagle-import:R0805")
      (libsource (lib "eagle-import") (part "R-EU_R0805"))
    )
    (comp (ref "R28")
      (value "100R")
      (footprint "eagle-import:R0805")
      (libsource (lib "eagle-import") (part "R-EU_R0805"))
    )
    (comp (ref "R29")
      (value "22R/2W")
      (footprint "eagle-import:R2512")
      (libsource (lib "eagle-import") (part "R-EU_R2512"))
    )
    (comp (ref "R30")
      (value "100R")
      (footprint "eagle-import:R0805")
      (libsource (lib "eagle-import") (part "R-EU_R0805"))
    )
    (comp (ref "R31")
      (value "22R/2W")
      (footprint "eagle-import:R2512")
      (libsource (lib "eagle-import") (part "R-EU_R2512"))
    )
    (comp (ref "R32")
      (value "1R")
      (footprint "eagle-import:R0805")
      (libsource (lib "eagle-import") (part "R-EU_R0805"))
    )
    (comp (ref "R33")
      (value "30K")
      (footprint "eagle-import:R0805")
      (libsource (lib "eagle-import") (part "R-EU_R0805"))
    )
    (comp (ref "R34")
      (value "10R")
      (footprint "eagle-import:R0805")
      (libsource (lib "eagle-import") (part "R-EU_R0805"))
    )
    (comp (ref "R35")
      (value "10R")
      (footprint "eagle-import:R0805")
      (libsource (lib "eagle-import") (part "R-EU_R0805"))
    )
    (comp (ref "R36")
      (value "10R")
      (footprint "eagle-import:R0805")
      (libsource (lib "eagle-import") (part "R-EU_R0805"))
    )
    (comp (ref "R37")
      (value "47K")
      (footprint "eagle-import:R0805")
      (libsource (lib "eagle-import") (part "R-EU_R0805"))
    )
    (comp (ref "R38")
      (value "220K")
      (footprint "eagle-import:R1206")
      (libsource (lib "eagle-import") (part "R-EU_R1206"))
    )
    (comp (ref "R39")
      (value "1R")
      (footprint "eagle-import:R0805")
      (libsource (lib "eagle-import") (part "R-EU_R0805"))
    )
    (comp (ref "R40")
      (value "22R/2W")
      (footprint "eagle-import:R2512")
      (libsource (lib "eagle-import") (part "R-EU_R2512"))
    )
    (comp (ref "R41")
      (value "22R/2W")
      (footprint "eagle-import:R2512")
      (libsource (lib "eagle-import") (part "R-EU_R2512"))
    )
    (comp (ref "R42")
      (value "100K")
      (footprint "eagle-import:R0805")
      (libsource (lib "eagle-import") (part "R-EU_R0805"))
    )
    (comp (ref "R43")
      (value "10R")
      (footprint "eagle-import:R0805")
      (libsource (lib "eagle-import") (part "R-EU_R0805"))
    )
    (comp (ref "R44")
      (value "1K")
      (footprint "eagle-import:R0805")
      (libsource (lib "eagle-import") (part "R-EU_R0805"))
    )
    (comp (ref "R45")
      (value "6K8")
      (footprint "eagle-import:R0805")
      (libsource (lib "eagle-import") (part "R-EU_R0805"))
    )
    (comp (ref "R46")
      (value "22R")
      (footprint "eagle-import:R0805")
      (libsource (lib "eagle-import") (part "R-EU_R0805"))
    )
    (comp (ref "R47")
      (value "22R")
      (footprint "eagle-import:R0805")
      (libsource (lib "eagle-import") (part "R-EU_R0805"))
    )
    (comp (ref "R48")
      (value "30K")
      (footprint "eagle-import:R0805")
      (libsource (lib "eagle-import") (part "R-EU_R0805"))
    )
    (comp (ref "R49")
      (value "82K")
      (footprint "eagle-import:R0805")
      (libsource (lib "eagle-import") (part "R-EU_R0805"))
    )
    (comp (ref "R50")
      (value "6K8")
      (footprint "eagle-import:R0805")
      (libsource (lib "eagle-import") (part "R-EU_R0805"))
    )
    (comp (ref "R51")
      (value "1K")
      (footprint "eagle-import:R0805")
      (libsource (lib "eagle-import") (part "R-EU_R0805"))
    )
    (comp (ref "R52")
      (value "6K8")
      (footprint "eagle-import:R0805")
      (libsource (lib "eagle-import") (part "R-EU_R0805"))
    )
    (comp (ref "R53")
      (value "N.C.")
      (footprint "eagle-import:R0805")
      (libsource (lib "eagle-import") (part "R-EU_R0805"))
    )
    (comp (ref "SH1")
      (value "SHORTNOHOLE")
      (footprint "eagle-import:SHORT_NOHOLE")
      (libsource (lib "eagle-import") (part "SHORTNOHOLE"))
    )
    (comp (ref "TP3")
      (value "PCB_TEST_TABSHIELD")
      (footprint "eagle-import:PCB_SHIELD_TAB")
      (libsource (lib "eagle-import") (part "PCB_TEST_TABSHIELD"))
    )
    (comp (ref "TP4")
      (value "PCB_TEST_TABSHIELD")
      (footprint "eagle-import:PCB_SHIELD_TAB")
      (libsource (lib "eagle-import") (part "PCB_TEST_TABSHIELD"))
    )
    (comp (ref "TP5")
      (value "PCB_TEST_TABSHIELD")
      (footprint "eagle-import:PCB_SHIELD_TAB")
      (libsource (lib "eagle-import") (part "PCB_TEST_TABSHIELD"))
    )
    (comp (ref "TP6")
      (value "PCB_TEST_TABSHIELD")
      (footprint "eagle-import:PCB_SHIELD_TAB")
      (libsource (lib "eagle-import") (part "PCB_TEST_TABSHIELD"))
    )
    (comp (ref "TR2")
      (value "53100C")
      (footprint "eagle-import:MURATA_5300")
      (libsource (lib "eagle-import") (part "MURATA_5300"))
    )
    (comp (ref "TR3")
      (value "VAC T60006-L2025-W380")
      (footprint "eagle-import:VAC_DUAL_SEC")
      (libsource (lib "eagle-import") (part "PCB_TRAFO_FLYBACK2-VAC"))
    )
    (comp (ref "ZD4")
      (value "MMSZ5V1T1G")
      (footprint "eagle-import:SOD323-W")
      (libsource (lib "eagle-import") (part "ZENER-DIODESOD323"))
    )
    (comp (ref "ZD5")
      (value "PDZ6.2B")
      (footprint "eagle-import:SOD323-W")
      (libsource (lib "eagle-import") (part "ZENER-DIODESOD323"))
    )
  )
  (nets
    (net (code "1") (name "+6V") (class "Default")
      (node (ref "C22") (pin "1") (pinfunction "1_1") (pintype "passive"))
      (node (ref "C25") (pin "1") (pinfunction "1_1") (pintype "passive"))
      (node (ref "D7") (pin "C") (pinfunction "C_C") (pintype "passive"))
      (node (ref "IC2") (pin "8") (pinfunction "IN_8") (pintype "power_in"))
      (node (ref "L4") (pin "2") (pinfunction "2_2") (pintype "passive"))
      (node (ref "LED1") (pin "A") (pinfunction "A_A") (pintype "passive"))
      (node (ref "R22") (pin "2") (pinfunction "2_2") (pintype "passive"))
      (node (ref "R59") (pin "1") (pinfunction "1_1") (pintype "passive"))
    )
    (net (code "2") (name "+12V") (class "Default")
      (node (ref "C29") (pin "2") (pinfunction "2_2") (pintype "passive"))
      (node (ref "C30") (pin "2") (pinfunction "2_2") (pintype "passive"))
      (node (ref "C4") (pin "1") (pinfunction "1_1") (pintype "passive"))
      (node (ref "Q1") (pin "3") (pinfunction "E_3") (pintype "passive"))
      (node (ref "R26") (pin "2") (pinfunction "2_2") (pintype "passive"))
      (node (ref "R36") (pin "2") (pinfunction "2_2") (pintype "passive"))
      (node (ref "R43") (pin "2") (pinfunction "2_2") (pintype "passive"))
      (node (ref "X1") (pin "1") (pinfunction "1_1") (pintype "passive"))
    )
    (net (code "3") (name "0V") (class "Default")
      (node (ref "C13") (pin "-") (pinfunction "-_-") (pintype "passive"))
      (node (ref "C20") (pin "1") (pinfunction "1_1") (pintype "passive"))
      (node (ref "C27") (pin "2") (pinfunction "2_2") (pintype "passive"))
      (node (ref "C28") (pin "2") (pinfunction "2_2") (pintype "passive"))
      (node (ref "C29") (pin "1") (pinfunction "1_1") (pintype "passive"))
      (node (ref "C30") (pin "1") (pinfunction "1_1") (pintype "passive"))
      (node (ref "C31") (pin "-") (pinfunction "-_-") (pintype "passive"))
      (node (ref "C32") (pin "-") (pinfunction "-_-") (pintype "passive"))
      (node (ref "C36") (pin "1") (pinfunction "1_1") (pintype "passive"))
      (node (ref "C38") (pin "2") (pinfunction "2_2") (pintype "passive"))
      (node (ref "C39") (pin "2") (pinfunction "2_2") (pintype "passive"))
      (node (ref "C4") (pin "2") (pinfunction "2_2") (pintype "passive"))
      (node (ref "C40") (pin "2") (pinfunction "2_2") (pintype "passive"))
      (node (ref "C43") (pin "2") (pinfunction "2_2") (pintype "passive"))
      (node (ref "C44") (pin "2") (pinfunction "2_2") (pintype "passive"))
      (node (ref "C46") (pin "1") (pinfunction "1_1") (pintype "passive"))
      (node (ref "C47") (pin "1") (pinfunction "1_1") (pintype "passive"))
      (node (ref "C7") (pin "2") (pinfunction "-_2") (pintype "passive"))
      (node (ref "C8") (pin "2") (pinfunction "2_2") (pintype "passive"))
      (node (ref "D11") (pin "A") (pinfunction "A_A") (pintype "passive"))
      (node (ref "D15") (pin "2") (pinfunction "A_2") (pintype "passive"))
      (node (ref "IC3") (pin "1") (pinfunction "GND_1") (pintype "passive"))
      (node (ref "IC3") (pin "2") (pinfunction "GND_2") (pintype "passive"))
      (node (ref "IC3") (pin "3") (pinfunction "GND_3") (pintype "passive"))
      (node (ref "IC3") (pin "4") (pinfunction "GND_4") (pintype "passive"))
      (node (ref "IC4") (pin "9") (pinfunction "GNDB_9") (pintype "power_in"))
      (node (ref "JP2") (pin "NC") (pinfunction "NC_NC") (pintype "passive"))
      (node (ref "JP3") (pin "1") (pinfunction "1_1") (pintype "passive"))
      (node (ref "OK1") (pin "3") (pinfunction "EMIT_3") (pintype "passive"))
      (node (ref "Q3") (pin "S") (pinfunction "S_S") (pintype "passive"))
      (node (ref "Q4") (pin "S") (pinfunction "S_S") (pintype "passive"))
      (node (ref "Q5") (pin "S") (pinfunction "S_S") (pintype "passive"))
      (node (ref "R19") (pin "1") (pinfunction "1_1") (pintype "passive"))
      (node (ref "R20") (pin "2") (pinfunction "2_2") (pintype "passive"))
      (node (ref "R21") (pin "2") (pinfunction "2_2") (pintype "passive"))
      (node (ref "R37") (pin "2") (pinfunction "2_2") (pintype "passive"))
      (node (ref "R39") (pin "1") (pinfunction "1_1") (pintype "passive"))
      (node (ref "R39") (pin "2") (pinfunction "2_2") (pintype "passive"))
      (node (ref "SH1") (pin "P$2") (pinfunction "GND_B_P$2") (pintype "bidirectional"))
      (node (ref "TP1") (pin "1") (pinfunction "P$1_1") (pintype "bidirectional"))
      (node (ref "TP4") (pin "1") (pinfunction "P$1_1") (pintype "bidirectional"))
      (node (ref "TR1") (pin "6") (pinfunction "S_BIAS_6") (pintype "passive"))
      (node (ref "X1") (pin "2") (pinfunction "1_2") (pintype "passive"))
      (node (ref "ZD1") (pin "A") (pinfunction "A_A") (pintype "passive"))
      (node (ref "ZD2") (pin "A") (pinfunction "A_A") (pintype "passive"))
    )
    (net (code "4") (name "AGND") (class "Default")
      (node (ref "C37") (pin "1") (pinfunction "1_1") (pintype "passive"))
      (node (ref "C42") (pin "2") (pinfunction "2_2") (pintype "passive"))
      (node (ref "C45") (pin "1") (pinfunction "1_1") (pintype "passive"))
      (node (ref "C48") (pin "1") (pinfunction "1_1") (pintype "passive"))
      (node (ref "C49") (pin "1") (pinfunction "1_1") (pintype "passive"))
      (node (ref "C50") (pin "1") (pinfunction "1_1") (pintype "passive"))
      (node (ref "C51") (pin "1") (pinfunction "1_1") (pintype "passive"))
      (node (ref "IC4") (pin "4") (pinfunction "GNDI_4") (pintype "power_in"))
      (node (ref "IC4") (pin "5") (pinfunction "DISABLE_5") (pintype "input"))
      (node (ref "IC5") (pin "10") (pinfunction "PGND_10") (pintype "power_in"))
      (node (ref "IC5") (pin "11") (pinfunction "AGND_11") (pintype "power_in"))
      (node (ref "IC5") (pin "2") (pinfunction "FB_2") (pintype "input"))
      (node (ref "JP3") (pin "2") (pinfunction "2_2") (pintype "passive"))
      (node (ref "OK2") (pin "3") (pinfunction "EMIT_3") (pintype "passive"))
      (node (ref "Q6") (pin "C") (pinfunction "C_C") (pintype "passive"))
      (node (ref "R23") (pin "2") (pinfunction "2_2") (pintype "passive"))
      (node (ref "R24") (pin "2") (pinfunction "2_2") (pintype "passive"))
      (node (ref "R25") (pin "2") (pinfunction "2_2") (pintype "passive"))
      (node (ref "R32") (pin "1") (pinfunction "1_1") (pintype "passive"))
      (node (ref "R32") (pin "2") (pinfunction "2_2") (pintype "passive"))
      (node (ref "R33") (pin "1") (pinfunction "1_1") (pintype "passive"))
      (node (ref "R45") (pin "2") (pinfunction "2_2") (pintype "passive"))
      (node (ref "R48") (pin "2") (pinfunction "2_2") (pintype "passive"))
      (node (ref "R49") (pin "2") (pinfunction "2_2") (pintype "passive"))
      (node (ref "R52") (pin "2") (pinfunction "2_2") (pintype "passive"))
      (node (ref "TR2") (pin "1") (pinfunction "S_DOT_1") (pintype "passive"))
      (node (ref "ZD4") (pin "A") (pinfunction "A_A") (pintype "passive"))
      (node (ref "ZD5") (pin "A") (pinfunction "A_A") (pintype "passive"))
    )
    (net (code "5") (name "AUX") (class "Default")
      (node (ref "C3") (pin "2") (pinfunction "2_2") (pintype "passive"))
      (node (ref "D1") (pin "A") (pinfunction "A_A") (pintype "passive"))
      (node (ref "D10") (pin "A") (pinfunction "A_A") (pintype "passive"))
      (node (ref "R15") (pin "2") (pinfunction "2_2") (pintype "passive"))
      (node (ref "TR1") (pin "7") (pinfunction "S_BIAS_DOT_7") (pintype "passive"))
    )
    (net (code "6") (name "AUX_OUT") (class "Default")
      (node (ref "C20") (pin "2") (pinfunction "2_2") (pintype "passive"))
      (node (ref "C7") (pin "1") (pinfunction "+_1") (pintype "passive"))
      (node (ref "IC3") (pin "5") (pinfunction "VDD_5") (pintype "power_in"))
      (node (ref "Q1") (pin "2") (pinfunction "C_2") (pintype "passive"))
      (node (ref "Q1") (pin "4") (pinfunction "C_4") (pintype "passive"))
      (node (ref "R4") (pin "2") (pinfunction "2_2") (pintype "passive"))
      (node (ref "R5") (pin "1") (pinfunction "1_1") (pintype "passive"))
      (node (ref "ZD1") (pin "C") (pinfunction "C_C") (pintype "passive"))
    )
    (net (code "7") (name "BUCK_OUT") (class "Default")
      (node (ref "C33") (pin "2") (pinfunction "2_2") (pintype "passive"))
      (node (ref "C34") (pin "2") (pinfunction "2_2") (pintype "passive"))
      (node (ref "C35") (pin "2") (pinfunction "2_2") (pintype "passive"))
      (node (ref "D15") (pin "1") (pinfunction "C_1") (pintype "passive"))
      (node (ref "IC4") (pin "14") (pinfunction "GNDA_14") (pintype "power_in"))
      (node (ref "L5") (pin "2") (pinfunction "P$2_2") (pintype "bidirectional"))
      (node (ref "L6") (pin "2") (pinfunction "P$2_2") (pintype "bidirectional"))
      (node (ref "Q2") (pin "S") (pinfunction "S_S") (pintype "passive"))
      (node (ref "Q3") (pin "D") (pinfunction "D_D") (pintype "passive"))
      (node (ref "TP3") (pin "1") (pinfunction "P$1_1") (pintype "bidirectional"))
    )
    (net (code "8") (name "CT_OUT") (class "Default")
      (node (ref "D12") (pin "C") (pinfunction "C_C") (pintype "passive"))
      (node (ref "R24") (pin "1") (pinfunction "1_1") (pintype "passive"))
      (node (ref "R25") (pin "1") (pinfunction "1_1") (pintype "passive"))
      (node (ref "R51") (pin "1") (pinfunction "1_1") (pintype "passive"))
    )
    (net (code "9") (name "DC_BUS") (class "Default")
      (node (ref "B1") (pin "+") (pinfunction "+_+") (pintype "passive"))
      (node (ref "C12") (pin "1") (pinfunction "1_1") (pintype "passive"))
      (node (ref "C13") (pin "+") (pinfunction "+_+") (pintype "passive"))
      (node (ref "C31") (pin "+") (pinfunction "+_+") (pintype "passive"))
      (node (ref "C32") (pin "+") (pinfunction "+_+") (pintype "passive"))
      (node (ref "C36") (pin "2") (pinfunction "2_2") (pintype "passive"))
      (node (ref "R38") (pin "1") (pinfunction "1_1") (pintype "passive"))
      (node (ref "R40") (pin "2") (pinfunction "2_2") (pintype "passive"))
      (node (ref "R41") (pin "2") (pinfunction "2_2") (pintype "passive"))
      (node (ref "R7") (pin "1") (pinfunction "1_1") (pintype "passive"))
      (node (ref "R8") (pin "1") (pinfunction "1_1") (pintype "passive"))
      (node (ref "TR1") (pin "1") (pinfunction "SHIELD_1") (pintype "passive"))
      (node (ref "TR1") (pin "2") (pinfunction "P_2") (pintype "passive"))
      (node (ref "TR2") (pin "7") (pinfunction "P_7") (pintype "passive"))
    )
    (net (code "10") (name "DC_OUT") (class "Default")
      (node (ref "C11") (pin "1") (pinfunction "1_1") (pintype "passive"))
      (node (ref "L2") (pin "2") (pinfunction "2_2") (pintype "passive"))
      (node (ref "X3") (pin "3") (pinfunction "S_3") (pintype "passive"))
    )
    (net (code "11") (name "GND") (class "Default")
      (node (ref "C14") (pin "1") (pinfunction "+_1") (pintype "passive"))
      (node (ref "C15") (pin "1") (pinfunction "1_1") (pintype "passive"))
      (node (ref "C16") (pin "1") (pinfunction "1_1") (pintype "passive"))
      (node (ref "C17") (pin "1") (pinfunction "1_1") (pintype "passive"))
      (node (ref "C19") (pin "2") (pinfunction "2_2") (pintype "passive"))
      (node (ref "C22") (pin "2") (pinfunction "2_2") (pintype "passive"))
      (node (ref "C23") (pin "-") (pinfunction "-_-") (pintype "passive"))
      (node (ref "C24") (pin "-") (pinfunction "-_-") (pintype "passive"))
      (node (ref "C25") (pin "2") (pinfunction "2_2") (pintype "passive"))
      (node (ref "C52") (pin "-") (pinfunction "-_-") (pintype "passive"))
      (node (ref "C53") (pin "-") (pinfunction "-_-") (pintype "passive"))
      (node (ref "C54") (pin "-") (pinfunction "-_-") (pintype "passive"))
      (node (ref "C55") (pin "2") (pinfunction "2_2") (pintype "passive"))
      (node (ref "C56") (pin "2") (pinfunction "2_2") (pintype "passive"))
      (node (ref "C57") (pin "2") (pinfunction "2_2") (pintype "passive"))
      (node (ref "C58") (pin "2") (pinfunction "2_2") (pintype "passive"))
      (node (ref "C59") (pin "2") (pinfunction "2_2") (pintype "passive"))
      (node (ref "C60") (pin "1") (pinfunction "1_1") (pintype "passive"))
      (node (ref "C61") (pin "2") (pinfunction "2_2") (pintype "passive"))
      (node (ref "C62") (pin "2") (pinfunction "2_2") (pintype "passive"))
      (node (ref "C63") (pin "2") (pinfunction "2_2") (pintype "passive"))
      (node (ref "C64") (pin "2") (pinfunction "2_2") (pintype "passive"))
      (node (ref "C65") (pin "2") (pinfunction "2_2") (pintype "passive"))
      (node (ref "C66") (pin "2") (pinfunction "2_2") (pintype "passive"))
      (node (ref "C67") (pin "2") (pinfunction "2_2") (pintype "passive"))
      (node (ref "C71") (pin "-") (pinfunction "-_-") (pintype "passive"))
      (node (ref "C72") (pin "2") (pinfunction "2_2") (pintype "passive"))
      (node (ref "D3") (pin "C") (pinfunction "C_C") (pintype "passive"))
      (node (ref "D9") (pin "A") (pinfunction "A_A") (pintype "passive"))
      (node (ref "IC1") (pin "5") (pinfunction "GND_5") (pintype "passive"))
      (node (ref "IC2") (pin "4") (pinfunction "GND_4") (pintype "passive"))
      (node (ref "IC6") (pin "6") (pinfunction "VS_6") (pintype "passive"))
      (node (ref "IC6") (pin "7") (pinfunction "GND_7") (pintype "power_in"))
      (node (ref "IC7") (pin "3") (pinfunction "+IN_3") (pintype "input"))
      (node (ref "IC7") (pin "5") (pinfunction "+IN_5") (pintype "input"))
      (node (ref "IC8") (pin "4") (pinfunction "VCC-_4") (pintype "power_in"))
      (node (ref "IC9") (pin "3") (pinfunction "A_3") (pintype "passive"))
      (node (ref "JP1") (pin "NO") (pinfunction "NO_NO") (pintype "passive"))
      (node (ref "P1") (pin "A") (pinfunction "A_A") (pintype "passive"))
      (node (ref "Q7") (pin "2") (pinfunction "S_2") (pintype "passive"))
      (node (ref "Q8") (pin "2") (pinfunction "S_2") (pintype "passive"))
      (node (ref "R13") (pin "2") (pinfunction "2_2") (pintype "passive"))
      (node (ref "R14") (pin "2") (pinfunction "2_2") (pintype "passive"))
      (node (ref "R60") (pin "2") (pinfunction "2_2") (pintype "passive"))
      (node (ref "R80") (pin "1") (pinfunction "1_1") (pintype "passive"))
      (node (ref "TP2") (pin "1") (pinfunction "P$1_1") (pintype "bidirectional"))
      (node (ref "TP7") (pin "GND") (pinfunction "GND_GND") (pintype "bidirectional"))
      (node (ref "TR1") (pin "10") (pinfunction "S1_10") (pintype "passive"))
      (node (ref "TR1") (pin "11") (pinfunction "S1_11") (pintype "passive"))
      (node (ref "TR1") (pin "9") (pinfunction "S2_DOT_9") (pintype "passive"))
      (node (ref "X3") (pin "6") (pinfunction "S_6") (pintype "passive"))
      (node (ref "X4") (pin "2") (pinfunction "1_2") (pintype "passive"))
      (node (ref "ZD3") (pin "A") (pinfunction "A_A") (pintype "passive"))
      (node (ref "ZD6") (pin "A") (pinfunction "A_A") (pintype "passive"))
    )
    (net (code "12") (name "GNDA") (class "Default")
      (node (ref "B1") (pin "-") (pinfunction "-_-") (pintype "passive"))
      (node (ref "SH1") (pin "P$1") (pinfunction "GND_A_P$1") (pintype "bidirectional"))
    )
    (net (code "13") (name "HD") (class "Default")
      (node (ref "IC5") (pin "5") (pinfunction "HD_5") (pintype "output"))
      (node (ref "R28") (pin "2") (pinfunction "2_2") (pintype "passive"))
    )
    (net (code "14") (name "HI_OUT") (class "Default")
      (node (ref "D14") (pin "A") (pinfunction "A_A") (pintype "passive"))
      (node (ref "IC4") (pin "15") (pinfunction "VOA_15") (pintype "output"))
      (node (ref "R27") (pin "2") (pinfunction "2_2") (pintype "passive"))
    )
    (net (code "15") (name "ISO_FB") (class "Default")
      (node (ref "C50") (pin "2") (pinfunction "2_2") (pintype "passive"))
      (node (ref "IC5") (pin "3") (pinfunction "COMP_3") (pintype "passive"))
      (node (ref "OK2") (pin "4") (pinfunction "COL_4") (pintype "passive"))
      (node (ref "Q6") (pin "E") (pinfunction "E_E") (pintype "passive"))
      (node (ref "R53") (pin "1") (pinfunction "1_1") (pintype "passive"))
      (node (ref "TP6") (pin "1") (pinfunction "P$1_1") (pintype "bidirectional"))
    )
    (net (code "16") (name "LD") (class "Default")
      (node (ref "IC5") (pin "6") (pinfunction "LD_6") (pintype "output"))
      (node (ref "R30") (pin "2") (pinfunction "2_2") (pintype "passive"))
    )
    (net (code "17") (name "LO_OUT") (class "Default")
      (node (ref "D17") (pin "A") (pinfunction "A_A") (pintype "passive"))
      (node (ref "IC4") (pin "10") (pinfunction "VOB_10") (pintype "output"))
      (node (ref "R34") (pin "1") (pinfunction "1_1") (pintype "passive"))
    )
    (net (code "18") (name "Net-(C3-Pad1)") (class "Default")
      (node (ref "C3") (pin "1") (pinfunction "1_1") (pintype "passive"))
      (node (ref "R2") (pin "2") (pinfunction "2_2") (pintype "passive"))
    )
    (net (code "19") (name "Net-(C9-Pad1)") (class "Default")
      (node (ref "C9") (pin "1") (pinfunction "1_1") (pintype "passive"))
      (node (ref "R6") (pin "2") (pinfunction "2_2") (pintype "passive"))
    )
    (net (code "20") (name "Net-(C10-+)") (class "Default")
      (node (ref "C10") (pin "1") (pinfunction "+_1") (pintype "passive"))
      (node (ref "D2") (pin "C") (pinfunction "C_C") (pintype "passive"))
      (node (ref "L2") (pin "1") (pinfunction "1_1") (pintype "passive"))
      (node (ref "R6") (pin "1") (pinfunction "1_1") (pintype "passive"))
    )
    (net (code "21") (name "Net-(C10--)") (class "Default")
      (node (ref "C10") (pin "2") (pinfunction "-_2") (pintype "passive"))
      (node (ref "C11") (pin "2") (pinfunction "2_2") (pintype "passive"))
      (node (ref "JP1") (pin "COM") (pinfunction "COM_COM") (pintype "passive"))
      (node (ref "TR1") (pin "14") (pinfunction "S3_14") (pintype "passive"))
    )
    (net (code "22") (name "Net-(C12-Pad2)") (class "Default")
      (node (ref "C12") (pin "2") (pinfunction "2_2") (pintype "passive"))
      (node (ref "D4") (pin "C") (pinfunction "C_C") (pintype "passive"))
      (node (ref "R7") (pin "2") (pinfunction "2_2") (pintype "passive"))
    )
    (net (code "23") (name "Net-(C14--)") (class "Default")
      (node (ref "C14") (pin "2") (pinfunction "-_2") (pintype "passive"))
      (node (ref "D5") (pin "A") (pinfunction "A_A") (pintype "passive"))
      (node (ref "L3") (pin "1") (pinfunction "1_1") (pintype "passive"))
      (node (ref "R10") (pin "1") (pinfunction "1_1") (pintype "passive"))
    )
    (net (code "24") (name "Net-(C18-Pad1)") (class "Default")
      (node (ref "C18") (pin "1") (pinfunction "1_1") (pintype "passive"))
      (node (ref "R10") (pin "2") (pinfunction "2_2") (pintype "passive"))
    )
    (net (code "25") (name "Net-(C19-Pad1)") (class "Default")
      (node (ref "C19") (pin "1") (pinfunction "1_1") (pintype "passive"))
      (node (ref "JP2") (pin "COM") (pinfunction "COM_COM") (pintype "passive"))
    )
    (net (code "26") (name "Net-(C21-Pad1)") (class "Default")
      (node (ref "C21") (pin "1") (pinfunction "1_1") (pintype "passive"))
      (node (ref "R11") (pin "2") (pinfunction "2_2") (pintype "passive"))
    )
    (net (code "27") (name "Net-(C21-Pad2)") (class "Default")
      (node (ref "C21") (pin "2") (pinfunction "2_2") (pintype "passive"))
      (node (ref "D8") (pin "A") (pinfunction "A_A") (pintype "passive"))
      (node (ref "TR1") (pin "12") (pinfunction "S1_DOT_12") (pintype "passive"))
      (node (ref "TR1") (pin "13") (pinfunction "S1_DOT_13") (pintype "passive"))
    )
    (net (code "28") (name "Net-(C24-Pad+)") (class "Default")
      (node (ref "C24") (pin "+") (pinfunction "+_+") (pintype "passive"))
      (node (ref "D8") (pin "C") (pinfunction "C_C") (pintype "passive"))
      (node (ref "L4") (pin "1") (pinfunction "1_1") (pintype "passive"))
      (node (ref "R11") (pin "1") (pinfunction "1_1") (pintype "passive"))
      (node (ref "R18") (pin "1") (pinfunction "1_1") (pintype "passive"))
    )
    (net (code "29") (name "Net-(C26-Pad1)") (class "Default")
      (node (ref "C26") (pin "1") (pinfunction "1_1") (pintype "passive"))
      (node (ref "R21") (pin "1") (pinfunction "1_1") (pintype "passive"))
    )
    (net (code "30") (name "Net-(C41-Pad1)") (class "Default")
      (node (ref "C41") (pin "1") (pinfunction "1_1") (pintype "passive"))
      (node (ref "R31") (pin "1") (pinfunction "1_1") (pintype "passive"))
    )
    (net (code "31") (name "Net-(C46-Pad2)") (class "Default")
      (node (ref "C46") (pin "2") (pinfunction "2_2") (pintype "passive"))
      (node (ref "C47") (pin "2") (pinfunction "2_2") (pintype "passive"))
      (node (ref "D18") (pin "1") (pinfunction "C_1") (pintype "passive"))
      (node (ref "D18") (pin "3") (pinfunction "C_3") (pintype "passive"))
      (node (ref "D19") (pin "1") (pinfunction "C_1") (pintype "passive"))
      (node (ref "D19") (pin "3") (pinfunction "C_3") (pintype "passive"))
      (node (ref "R40") (pin "1") (pinfunction "1_1") (pintype "passive"))
      (node (ref "R41") (pin "1") (pinfunction "1_1") (pintype "passive"))
    )
    (net (code "32") (name "Net-(C51-Pad2)") (class "Default")
      (node (ref "C51") (pin "2") (pinfunction "2_2") (pintype "passive"))
      (node (ref "R53") (pin "2") (pinfunction "2_2") (pintype "passive"))
    )
    (net (code "33") (name "Net-(C60-Pad2)") (class "Default")
      (node (ref "C60") (pin "2") (pinfunction "2_2") (pintype "passive"))
      (node (ref "R55") (pin "1") (pinfunction "1_1") (pintype "passive"))
    )
    (net (code "34") (name "Net-(C61-Pad1)") (class "Default")
      (node (ref "C61") (pin "1") (pinfunction "1_1") (pintype "passive"))
      (node (ref "R56") (pin "2") (pinfunction "2_2") (pintype "passive"))
      (node (ref "R57") (pin "2") (pinfunction "2_2") (pintype "passive"))
    )
    (net (code "35") (name "Net-(C65-Pad1)") (class "Default")
      (node (ref "C65") (pin "1") (pinfunction "1_1") (pintype "passive"))
      (node (ref "R62") (pin "2") (pinfunction "2_2") (pintype "passive"))
      (node (ref "R63") (pin "2") (pinfunction "2_2") (pintype "passive"))
    )
    (net (code "36") (name "Net-(C70-Pad2)") (class "Default")
      (node (ref "C70") (pin "2") (pinfunction "2_2") (pintype "passive"))
      (node (ref "R74") (pin "2") (pinfunction "2_2") (pintype "passive"))
    )
    (net (code "37") (name "Net-(C71-Pad+)") (class "Default")
      (node (ref "C71") (pin "+") (pinfunction "+_+") (pintype "passive"))
      (node (ref "R67") (pin "1") (pinfunction "1_1") (pintype "passive"))
      (node (ref "R76") (pin "1") (pinfunction "1_1") (pintype "passive"))
      (node (ref "R77") (pin "1") (pinfunction "1_1") (pintype "passive"))
    )
    (net (code "38") (name "Net-(C74-Pad2)") (class "Default")
      (node (ref "C74") (pin "2") (pinfunction "2_2") (pintype "passive"))
      (node (ref "R79") (pin "1") (pinfunction "1_1") (pintype "passive"))
    )
    (net (code "39") (name "Net-(D1-PadC)") (class "Default")
      (node (ref "D1") (pin "C") (pinfunction "C_C") (pintype "passive"))
      (node (ref "R2") (pin "1") (pinfunction "1_1") (pintype "passive"))
      (node (ref "R4") (pin "1") (pinfunction "1_1") (pintype "passive"))
    )
    (net (code "40") (name "Net-(D10-PadC)") (class "Default")
      (node (ref "D10") (pin "C") (pinfunction "C_C") (pintype "passive"))
      (node (ref "D11") (pin "C") (pinfunction "C_C") (pintype "passive"))
      (node (ref "R17") (pin "2") (pinfunction "2_2") (pintype "passive"))
    )
    (net (code "41") (name "Net-(D13-A)") (class "Default")
      (node (ref "D13") (pin "2") (pinfunction "A_2") (pintype "passive"))
      (node (ref "R26") (pin "1") (pinfunction "1_1") (pintype "passive"))
    )
    (net (code "42") (name "Net-(D14-PadC)") (class "Default")
      (node (ref "D14") (pin "C") (pinfunction "C_C") (pintype "passive"))
      (node (ref "Q2") (pin "G") (pinfunction "G_G") (pintype "passive"))
      (node (ref "R27") (pin "1") (pinfunction "1_1") (pintype "passive"))
    )
    (net (code "43") (name "Net-(D16-PadA)") (class "Default")
      (node (ref "D16") (pin "A") (pinfunction "A_A") (pintype "passive"))
      (node (ref "R36") (pin "1") (pinfunction "1_1") (pintype "passive"))
    )
    (net (code "44") (name "Net-(D17-PadC)") (class "Default")
      (node (ref "D17") (pin "C") (pinfunction "C_C") (pintype "passive"))
      (node (ref "Q3") (pin "G") (pinfunction "G_G") (pintype "passive"))
      (node (ref "R34") (pin "2") (pinfunction "2_2") (pintype "passive"))
      (node (ref "R37") (pin "1") (pinfunction "1_1") (pintype "passive"))
    )
    (net (code "45") (name "Net-(D18-A)") (class "Default")
      (node (ref "C41") (pin "2") (pinfunction "2_2") (pintype "passive"))
      (node (ref "D18") (pin "2") (pinfunction "A_2") (pintype "passive"))
      (node (ref "L6") (pin "1") (pinfunction "P$1_1") (pintype "bidirectional"))
      (node (ref "Q5") (pin "D") (pinfunction "D_D") (pintype "passive"))
      (node (ref "TR3") (pin "P1_DOT") (pinfunction "P_DOT_P1_DOT") (pintype "passive"))
    )
    (net (code "46") (name "Net-(D19-A)") (class "Default")
      (node (ref "D19") (pin "2") (pinfunction "A_2") (pintype "passive"))
      (node (ref "L5") (pin "1") (pinfunction "P$1_1") (pintype "bidirectional"))
      (node (ref "Q4") (pin "D") (pinfunction "D_D") (pintype "passive"))
      (node (ref "R29") (pin "2") (pinfunction "2_2") (pintype "passive"))
      (node (ref "TR3") (pin "P1") (pinfunction "P_P1") (pintype "passive"))
    )
    (net (code "47") (name "Net-(D20-PadC)") (class "Default")
      (node (ref "D20") (pin "C") (pinfunction "C_C") (pintype "passive"))
      (node (ref "Q4") (pin "G") (pinfunction "G_G") (pintype "passive"))
      (node (ref "R46") (pin "1") (pinfunction "1_1") (pintype "passive"))
    )
    (net (code "48") (name "Net-(D21-PadC)") (class "Default")
      (node (ref "D21") (pin "C") (pinfunction "C_C") (pintype "passive"))
      (node (ref "Q5") (pin "G") (pinfunction "G_G") (pintype "passive"))
      (node (ref "R47") (pin "1") (pinfunction "1_1") (pintype "passive"))
    )
    (net (code "49") (name "Net-(IC2-FB)") (class "Default")
      (node (ref "IC2") (pin "7") (pinfunction "FB_7") (pintype "input"))
      (node (ref "R12") (pin "2") (pinfunction "2_2") (pintype "passive"))
      (node (ref "R13") (pin "1") (pinfunction "1_1") (pintype "passive"))
    )
    (net (code "50") (name "Net-(IC2-~{ERROR})") (class "Default")
      (node (ref "IC2") (pin "5") (pinfunction "~{ERROR}_5") (pintype "input"))
      (node (ref "R16") (pin "2") (pinfunction "2_2") (pintype "passive"))
      (node (ref "X3") (pin "4") (pinfunction "S_4") (pintype "passive"))
    )
    (net (code "51") (name "Net-(IC3-BR)") (class "Default")
      (node (ref "IC3") (pin "8") (pinfunction "BR_8") (pintype "input"))
      (node (ref "R20") (pin "1") (pinfunction "1_1") (pintype "passive"))
      (node (ref "R9") (pin "2") (pinfunction "2_2") (pintype "passive"))
    )
    (net (code "52") (name "Net-(IC3-FB)") (class "Default")
      (node (ref "C26") (pin "2") (pinfunction "2_2") (pintype "passive"))
      (node (ref "C28") (pin "1") (pinfunction "1_1") (pintype "passive"))
      (node (ref "IC3") (pin "7") (pinfunction "FB_7") (pintype "input"))
      (node (ref "OK1") (pin "4") (pinfunction "COL_4") (pintype "passive"))
    )
    (net (code "53") (name "Net-(IC3-ZCD)") (class "Default")
      (node (ref "C27") (pin "1") (pinfunction "1_1") (pintype "passive"))
      (node (ref "IC3") (pin "6") (pinfunction "ZCD_6") (pintype "input"))
      (node (ref "R15") (pin "1") (pinfunction "1_1") (pintype "passive"))
      (node (ref "R17") (pin "1") (pinfunction "1_1") (pintype "passive"))
      (node (ref "R19") (pin "2") (pinfunction "2_2") (pintype "passive"))
    )
    (net (code "54") (name "Net-(IC4-DT)") (class "Default")
      (node (ref "IC4") (pin "6") (pinfunction "DT_6") (pintype "input"))
      (node (ref "R33") (pin "2") (pinfunction "2_2") (pintype "passive"))
    )
    (net (code "55") (name "Net-(IC4-VDDA)") (class "Default")
      (node (ref "C33") (pin "1") (pinfunction "1_1") (pintype "passive"))
      (node (ref "C34") (pin "1") (pinfunction "1_1") (pintype "passive"))
      (node (ref "C35") (pin "1") (pinfunction "1_1") (pintype "passive"))
      (node (ref "D13") (pin "1") (pinfunction "C_1") (pintype "passive"))
      (node (ref "D13") (pin "3") (pinfunction "C_3") (pintype "passive"))
      (node (ref "IC4") (pin "16") (pinfunction "VDDA_16") (pintype "power_in"))
    )
    (net (code "56") (name "Net-(IC4-VDDB)") (class "Default")
      (node (ref "C38") (pin "1") (pinfunction "1_1") (pintype "passive"))
      (node (ref "C39") (pin "1") (pinfunction "1_1") (pintype "passive"))
      (node (ref "C40") (pin "1") (pinfunction "1_1") (pintype "passive"))
      (node (ref "D16") (pin "C") (pinfunction "C_C") (pintype "passive"))
      (node (ref "IC4") (pin "11") (pinfunction "VDDB_11") (pintype "power_in"))
    )
    (net (code "57") (name "Net-(IC4-VIA)") (class "Default")
      (node (ref "IC4") (pin "1") (pinfunction "VIA_1") (pintype "input"))
      (node (ref "R28") (pin "1") (pinfunction "1_1") (pintype "passive"))
    )
    (net (code "58") (name "Net-(IC4-VIB)") (class "Default")
      (node (ref "IC4") (pin "2") (pinfunction "VIB_2") (pintype "input"))
      (node (ref "R30") (pin "1") (pinfunction "1_1") (pintype "passive"))
    )
    (net (code "59") (name "Net-(IC5-CS)") (class "Default")
      (node (ref "C49") (pin "2") (pinfunction "2_2") (pintype "passive"))
      (node (ref "IC5") (pin "12") (pinfunction "CS_12") (pintype "input"))
      (node (ref "R51") (pin "2") (pinfunction "2_2") (pintype "passive"))
    )
    (net (code "60") (name "Net-(IC5-REF)") (class "Default")
      (node (ref "C48") (pin "2") (pinfunction "2_2") (pintype "passive"))
      (node (ref "IC5") (pin "4") (pinfunction "REF_4") (pintype "output"))
      (node (ref "R35") (pin "1") (pinfunction "1_1") (pintype "passive"))
      (node (ref "R50") (pin "1") (pinfunction "1_1") (pintype "passive"))
    )
    (net (code "61") (name "Net-(IC5-RT{slash}SYNC)") (class "Default")
      (node (ref "IC5") (pin "15") (pinfunction "RT/SYNC_15") (pintype "input"))
      (node (ref "R49") (pin "1") (pinfunction "1_1") (pintype "passive"))
    )
    (net (code "62") (name "Net-(IC5-SS)") (class "Default")
      (node (ref "C45") (pin "2") (pinfunction "2_2") (pintype "passive"))
      (node (ref "IC5") (pin "13") (pinfunction "SS_13") (pintype "passive"))
    )
    (net (code "63") (name "Net-(IC5-TIME)") (class "Default")
      (node (ref "IC5") (pin "14") (pinfunction "TIME_14") (pintype "input"))
      (node (ref "R48") (pin "1") (pinfunction "1_1") (pintype "passive"))
    )
    (net (code "64") (name "Net-(IC5-UVLO)") (class "Default")
      (node (ref "IC5") (pin "16") (pinfunction "UVLO_16") (pintype "input"))
      (node (ref "R44") (pin "1") (pinfunction "1_1") (pintype "passive"))
      (node (ref "ZD5") (pin "C") (pinfunction "C_C") (pintype "passive"))
    )
    (net (code "65") (name "Net-(IC5-VCC)") (class "Default")
      (node (ref "C43") (pin "1") (pinfunction "1_1") (pintype "passive"))
      (node (ref "C44") (pin "1") (pinfunction "1_1") (pintype "passive"))
      (node (ref "IC5") (pin "1") (pinfunction "VIN_1") (pintype "input"))
      (node (ref "IC5") (pin "7") (pinfunction "VCC_7") (pintype "power_in"))
      (node (ref "R43") (pin "1") (pinfunction "1_1") (pintype "passive"))
    )
    (net (code "66") (name "Net-(IC6-GATE1)") (class "Default")
      (node (ref "D22") (pin "C") (pinfunction "C_C") (pintype "passive"))
      (node (ref "IC6") (pin "1") (pinfunction "GATE1_1") (pintype "output"))
      (node (ref "R58") (pin "2") (pinfunction "2_2") (pintype "passive"))
    )
    (net (code "67") (name "Net-(IC6-GATE2)") (class "Default")
      (node (ref "D23") (pin "C") (pinfunction "C_C") (pintype "passive"))
      (node (ref "IC6") (pin "8") (pinfunction "GATE2_8") (pintype "output"))
      (node (ref "R61") (pin "2") (pinfunction "2_2") (pintype "passive"))
    )
    (net (code "68") (name "Net-(IC6-MOT)") (class "Default")
      (node (ref "IC6") (pin "3") (pinfunction "MOT_3") (pintype "passive"))
      (node (ref "R60") (pin "1") (pinfunction "1_1") (pintype "passive"))
    )
    (net (code "69") (name "Net-(IC6-VCC)") (class "Default")
      (node (ref "C62") (pin "1") (pinfunction "1_1") (pintype "passive"))
      (node (ref "C63") (pin "1") (pinfunction "1_1") (pintype "passive"))
      (node (ref "IC6") (pin "2") (pinfunction "VCC_2") (pintype "power_in"))
      (node (ref "R59") (pin "2") (pinfunction "2_2") (pintype "passive"))
    )
    (net (code "70") (name "Net-(IC7A--IN)") (class "Default")
      (node (ref "C68") (pin "2") (pinfunction "2_2") (pintype "passive"))
      (node (ref "IC7") (pin "2") (pinfunction "-IN_2") (pintype "input"))
      (node (ref "R68") (pin "2") (pinfunction "2_2") (pintype "passive"))
      (node (ref "R69") (pin "1") (pinfunction "1_1") (pintype "passive"))
      (node (ref "R73") (pin "1") (pinfunction "1_1") (pintype "passive"))
    )
    (net (code "71") (name "Net-(IC7A-OUT)") (class "Default")
      (node (ref "C68") (pin "1") (pinfunction "1_1") (pintype "passive"))
      (node (ref "IC7") (pin "1") (pinfunction "OUT_1") (pintype "output"))
      (node (ref "R77") (pin "2") (pinfunction "2_2") (pintype "passive"))
    )
    (net (code "72") (name "Net-(IC7B--IN)") (class "Default")
      (node (ref "IC7") (pin "6") (pinfunction "-IN_6") (pintype "input"))
      (node (ref "R64") (pin "2") (pinfunction "2_2") (pintype "passive"))
      (node (ref "R66") (pin "1") (pinfunction "1_1") (pintype "passive"))
    )
    (net (code "73") (name "Net-(IC7B-OUT)") (class "Default")
      (node (ref "IC7") (pin "7") (pinfunction "OUT_7") (pintype "output"))
      (node (ref "R64") (pin "1") (pinfunction "1_1") (pintype "passive"))
      (node (ref "R69") (pin "2") (pinfunction "2_2") (pintype "passive"))
    )
    (net (code "74") (name "Net-(IC8A-+IN1)") (class "Default")
      (node (ref "C72") (pin "1") (pinfunction "1_1") (pintype "passive"))
      (node (ref "IC8") (pin "3") (pinfunction "+IN1_3") (pintype "input"))
      (node (ref "P1") (pin "E") (pinfunction "E_E") (pintype "passive"))
      (node (ref "R66") (pin "2") (pinfunction "2_2") (pintype "passive"))
      (node (ref "R72") (pin "1") (pinfunction "1_1") (pintype "passive"))
    )
    (net (code "75") (name "Net-(IC8A--IN1)") (class "Default")
      (node (ref "C69") (pin "2") (pinfunction "2_2") (pintype "passive"))
      (node (ref "IC8") (pin "2") (pinfunction "-IN1_2") (pintype "input"))
      (node (ref "R74") (pin "1") (pinfunction "1_1") (pintype "passive"))
      (node (ref "R75") (pin "1") (pinfunction "1_1") (pintype "passive"))
    )
    (net (code "76") (name "Net-(IC8A-OUT1)") (class "Default")
      (node (ref "C69") (pin "1") (pinfunction "1_1") (pintype "passive"))
      (node (ref "C70") (pin "1") (pinfunction "1_1") (pintype "passive"))
      (node (ref "C73") (pin "1") (pinfunction "1_1") (pintype "passive"))
      (node (ref "C74") (pin "1") (pinfunction "1_1") (pintype "passive"))
      (node (ref "IC8") (pin "1") (pinfunction "OUT1_1") (pintype "output"))
      (node (ref "IC9") (pin "1") (pinfunction "C_1") (pintype "passive"))
      (node (ref "OK2") (pin "2") (pinfunction "C_2") (pintype "passive"))
      (node (ref "R78") (pin "2") (pinfunction "2_2") (pintype "passive"))
    )
    (net (code "77") (name "Net-(IC8B-+IN)") (class "Default")
      (node (ref "IC8") (pin "5") (pinfunction "+IN_5") (pintype "input"))
      (node (ref "JP4") (pin "COM") (pinfunction "COM_COM") (pintype "passive"))
    )
    (net (code "78") (name "Net-(IC8B--IN)") (class "Default")
      (node (ref "IC8") (pin "6") (pinfunction "-IN_6") (pintype "input"))
      (node (ref "IC8") (pin "7") (pinfunction "OUT_7") (pintype "output"))
      (node (ref "R73") (pin "2") (pinfunction "2_2") (pintype "passive"))
    )
    (net (code "79") (name "Net-(IC9-REF)") (class "Default")
      (node (ref "C73") (pin "2") (pinfunction "2_2") (pintype "passive"))
      (node (ref "IC9") (pin "2") (pinfunction "REF_2") (pintype "passive"))
      (node (ref "R71") (pin "1") (pinfunction "1_1") (pintype "passive"))
      (node (ref "R75") (pin "2") (pinfunction "2_2") (pintype "passive"))
      (node (ref "R76") (pin "2") (pinfunction "2_2") (pintype "passive"))
      (node (ref "R79") (pin "2") (pinfunction "2_2") (pintype "passive"))
      (node (ref "R80") (pin "2") (pinfunction "2_2") (pintype "passive"))
      (node (ref "TP8") (pin "1") (pinfunction "P$1_1") (pintype "bidirectional"))
    )
    (net (code "80") (name "Net-(JP4-PadNO)") (class "Default")
      (node (ref "JP4") (pin "NO") (pinfunction "NO_NO") (pintype "passive"))
      (node (ref "P1") (pin "S") (pinfunction "S_S") (pintype "passive"))
    )
    (net (code "81") (name "Net-(L1B-1)") (class "Default")
      (node (ref "B1") (pin "AC2") (pinfunction "AC2_AC2") (pintype "passive"))
      (node (ref "C2") (pin "2") (pinfunction "2_2") (pintype "passive"))
      (node (ref "C5") (pin "2") (pinfunction "2_2") (pintype "passive"))
      (node (ref "L1") (pin "3") (pinfunction "1_3") (pintype "passive"))
      (node (ref "SAR2") (pin "2") (pinfunction "P$2_2") (pintype "bidirectional"))
    )
    (net (code "82") (name "Net-(L1B-2)") (class "Default")
      (node (ref "C1") (pin "2") (pinfunction "2_2") (pintype "passive"))
      (node (ref "C5A") (pin "2") (pinfunction "2_2") (pintype "passive"))
      (node (ref "L1") (pin "4") (pinfunction "2_4") (pintype "passive"))
      (node (ref "R3") (pin "2") (pinfunction "2_2") (pintype "passive"))
      (node (ref "SAR2") (pin "1") (pinfunction "P$1_1") (pintype "bidirectional"))
      (node (ref "X2") (pin "3") (pinfunction "1_3") (pintype "passive"))
    )
    (net (code "83") (name "Net-(LED1-PadC)") (class "Default")
      (node (ref "LED1") (pin "C") (pinfunction "C_C") (pintype "passive"))
      (node (ref "R14") (pin "1") (pinfunction "1_1") (pintype "passive"))
    )
    (net (code "84") (name "Net-(OK1-A)") (class "Default")
      (node (ref "OK1") (pin "1") (pinfunction "A_1") (pintype "passive"))
      (node (ref "R18") (pin "2") (pinfunction "2_2") (pintype "passive"))
    )
    (net (code "85") (name "Net-(OK1-C)") (class "Default")
      (node (ref "OK1") (pin "2") (pinfunction "C_2") (pintype "passive"))
      (node (ref "R22") (pin "1") (pinfunction "1_1") (pintype "passive"))
      (node (ref "ZD3") (pin "C") (pinfunction "C_C") (pintype "passive"))
    )
    (net (code "86") (name "Net-(OK2-A)") (class "Default")
      (node (ref "OK2") (pin "1") (pinfunction "A_1") (pintype "passive"))
      (node (ref "R70") (pin "1") (pinfunction "1_1") (pintype "passive"))
      (node (ref "R78") (pin "1") (pinfunction "1_1") (pintype "passive"))
    )
    (net (code "87") (name "Net-(Q1-B)") (class "Default")
      (node (ref "C8") (pin "1") (pinfunction "1_1") (pintype "passive"))
      (node (ref "Q1") (pin "1") (pinfunction "B_1") (pintype "passive"))
      (node (ref "R5") (pin "2") (pinfunction "2_2") (pintype "passive"))
      (node (ref "ZD2") (pin "C") (pinfunction "C_C") (pintype "passive"))
    )
    (net (code "88") (name "Net-(Q6-PadB)") (class "Default")
      (node (ref "Q6") (pin "B") (pinfunction "B_B") (pintype "passive"))
      (node (ref "R50") (pin "2") (pinfunction "2_2") (pintype "passive"))
      (node (ref "R52") (pin "1") (pinfunction "1_1") (pintype "passive"))
    )
    (net (code "89") (name "Net-(R1-Pad2)") (class "Default")
      (node (ref "R1") (pin "2") (pinfunction "2_2") (pintype "passive"))
      (node (ref "R3") (pin "1") (pinfunction "1_1") (pintype "passive"))
    )
    (net (code "90") (name "Net-(R8-Pad2)") (class "Default")
      (node (ref "R8") (pin "2") (pinfunction "2_2") (pintype "passive"))
      (node (ref "R9") (pin "1") (pinfunction "1_1") (pintype "passive"))
    )
    (net (code "91") (name "Net-(R29-Pad1)") (class "Default")
      (node (ref "R29") (pin "1") (pinfunction "1_1") (pintype "passive"))
      (node (ref "R31") (pin "2") (pinfunction "2_2") (pintype "passive"))
    )
    (net (code "92") (name "Net-(R38-Pad2)") (class "Default")
      (node (ref "R38") (pin "2") (pinfunction "2_2") (pintype "passive"))
      (node (ref "R42") (pin "1") (pinfunction "1_1") (pintype "passive"))
    )
    (net (code "93") (name "Net-(R65-Pad1)") (class "Default")
      (node (ref "R65") (pin "1") (pinfunction "1_1") (pintype "passive"))
      (node (ref "R71") (pin "2") (pinfunction "2_2") (pintype "passive"))
    )
    (net (code "94") (name "Net-(R67-Pad2)") (class "Default")
      (node (ref "R67") (pin "2") (pinfunction "2_2") (pintype "passive"))
      (node (ref "R68") (pin "1") (pinfunction "1_1") (pintype "passive"))
    )
    (net (code "95") (name "Net-(SAR1-P$1)") (class "Default")
      (node (ref "C1") (pin "1") (pinfunction "1_1") (pintype "passive"))
      (node (ref "C6A") (pin "2") (pinfunction "2_2") (pintype "passive"))
      (node (ref "L1") (pin "2") (pinfunction "2_2") (pintype "passive"))
      (node (ref "R1") (pin "1") (pinfunction "1_1") (pintype "passive"))
      (node (ref "SAR1") (pin "1") (pinfunction "P$1_1") (pintype "bidirectional"))
      (node (ref "X2") (pin "2") (pinfunction "1_2") (pintype "passive"))
    )
    (net (code "96") (name "Net-(SAR1-P$2)") (class "Default")
      (node (ref "B1") (pin "AC1") (pinfunction "AC1_AC1") (pintype "passive"))
      (node (ref "C2") (pin "1") (pinfunction "1_1") (pintype "passive"))
      (node (ref "C6") (pin "2") (pinfunction "2_2") (pintype "passive"))
      (node (ref "L1") (pin "1") (pinfunction "1_1") (pintype "passive"))
      (node (ref "SAR1") (pin "2") (pinfunction "P$2_2") (pintype "bidirectional"))
    )
    (net (code "97") (name "Net-(TP5-P$1)") (class "Default")
      (node (ref "C42") (pin "1") (pinfunction "1_1") (pintype "passive"))
      (node (ref "R42") (pin "2") (pinfunction "2_2") (pintype "passive"))
      (node (ref "R44") (pin "2") (pinfunction "2_2") (pintype "passive"))
      (node (ref "R45") (pin "1") (pinfunction "1_1") (pintype "passive"))
      (node (ref "TP5") (pin "1") (pinfunction "P$1_1") (pintype "bidirectional"))
    )
    (net (code "98") (name "Net-(TR1-P2_DOT)") (class "Default")
      (node (ref "D4") (pin "A") (pinfunction "A_A") (pintype "passive"))
      (node (ref "IC3") (pin "13") (pinfunction "DRAIN_13") (pintype "output"))
      (node (ref "IC3") (pin "14") (pinfunction "DRAIN_14") (pintype "output"))
      (node (ref "IC3") (pin "15") (pinfunction "DRAIN_15") (pintype "output"))
      (node (ref "IC3") (pin "16") (pinfunction "DRAIN_16") (pintype "output"))
      (node (ref "TR1") (pin "4") (pinfunction "P2_DOT_4") (pintype "passive"))
    )
    (net (code "99") (name "Net-(TR1-S2)") (class "Default")
      (node (ref "C18") (pin "2") (pinfunction "2_2") (pintype "passive"))
      (node (ref "D5") (pin "C") (pinfunction "C_C") (pintype "passive"))
      (node (ref "TR1") (pin "8") (pinfunction "S2_8") (pintype "passive"))
    )
    (net (code "100") (name "Net-(TR1-S3_DOT)") (class "Default")
      (node (ref "C9") (pin "2") (pinfunction "2_2") (pintype "passive"))
      (node (ref "D2") (pin "A") (pinfunction "A_A") (pintype "passive"))
      (node (ref "TR1") (pin "15") (pinfunction "S3_DOT_15") (pintype "passive"))
    )
    (net (code "101") (name "Net-(TR2-P_DOT)") (class "Default")
      (node (ref "Q2") (pin "D") (pinfunction "D_D") (pintype "passive"))
      (node (ref "TR2") (pin "8") (pinfunction "P_DOT_8") (pintype "passive"))
    )
    (net (code "102") (name "Net-(TR2-S)") (class "Default")
      (node (ref "D12") (pin "A") (pinfunction "A_A") (pintype "passive"))
      (node (ref "R23") (pin "1") (pinfunction "1_1") (pintype "passive"))
      (node (ref "TR2") (pin "3") (pinfunction "S_3") (pintype "passive"))
    )
    (net (code "103") (name "Net-(X3H-S)") (class "Default")
      (node (ref "C15") (pin "2") (pinfunction "2_2") (pintype "passive"))
      (node (ref "C16") (pin "2") (pinfunction "2_2") (pintype "passive"))
      (node (ref "D6") (pin "A") (pinfunction "A_A") (pintype "passive"))
      (node (ref "IC1") (pin "2") (pinfunction "IN_2") (pintype "input"))
      (node (ref "IC1") (pin "3") (pinfunction "IN_3") (pintype "input"))
      (node (ref "IC1") (pin "6") (pinfunction "IN_6") (pintype "input"))
      (node (ref "IC1") (pin "7") (pinfunction "IN_7") (pintype "input"))
      (node (ref "L3") (pin "2") (pinfunction "2_2") (pintype "passive"))
      (node (ref "X3") (pin "8") (pinfunction "S_8") (pintype "passive"))
    )
    (net (code "104") (name "PE") (class "Default")
      (node (ref "C5") (pin "1") (pinfunction "1_1") (pintype "passive"))
      (node (ref "C5A") (pin "1") (pinfunction "1_1") (pintype "passive"))
      (node (ref "C6") (pin "1") (pinfunction "1_1") (pintype "passive"))
      (node (ref "C6A") (pin "1") (pinfunction "1_1") (pintype "passive"))
      (node (ref "JP2") (pin "NO") (pinfunction "NO_NO") (pintype "passive"))
      (node (ref "X2") (pin "1") (pinfunction "1_1") (pintype "passive"))
    )
    (net (code "105") (name "POUT+") (class "Default")
      (node (ref "C52") (pin "+") (pinfunction "+_+") (pintype "passive"))
      (node (ref "C53") (pin "+") (pinfunction "+_+") (pintype "passive"))
      (node (ref "C54") (pin "+") (pinfunction "+_+") (pintype "passive"))
      (node (ref "C55") (pin "1") (pinfunction "1_1") (pintype "passive"))
      (node (ref "L7") (pin "1") (pinfunction "1_1") (pintype "passive"))
      (node (ref "R54") (pin "1") (pinfunction "1_1") (pintype "passive"))
      (node (ref "R65") (pin "2") (pinfunction "2_2") (pintype "passive"))
      (node (ref "SH2") (pin "P$2") (pinfunction "GND_B_P$2") (pintype "bidirectional"))
      (node (ref "SH3") (pin "P$1") (pinfunction "GND_A_P$1") (pintype "bidirectional"))
    )
    (net (code "106") (name "PREG_OUT+") (class "Default")
      (node (ref "C56") (pin "1") (pinfunction "1_1") (pintype "passive"))
      (node (ref "C57") (pin "1") (pinfunction "1_1") (pintype "passive"))
      (node (ref "C58") (pin "1") (pinfunction "1_1") (pintype "passive"))
      (node (ref "C59") (pin "1") (pinfunction "1_1") (pintype "passive"))
      (node (ref "JP1") (pin "NC") (pinfunction "NC_NC") (pintype "passive"))
      (node (ref "L7") (pin "2") (pinfunction "2_2") (pintype "passive"))
      (node (ref "R54") (pin "2") (pinfunction "2_2") (pintype "passive"))
      (node (ref "R55") (pin "2") (pinfunction "2_2") (pintype "passive"))
      (node (ref "TP7") (pin "TIP") (pinfunction "TIP_TIP") (pintype "bidirectional"))
      (node (ref "X3") (pin "2") (pinfunction "S_2") (pintype "passive"))
      (node (ref "X4") (pin "1") (pinfunction "1_1") (pintype "passive"))
      (node (ref "ZD6") (pin "C") (pinfunction "C_C") (pintype "passive"))
    )
    (net (code "107") (name "PULL") (class "Default")
      (node (ref "D21") (pin "A") (pinfunction "A_A") (pintype "passive"))
      (node (ref "IC5") (pin "9") (pinfunction "PULL_9") (pintype "output"))
      (node (ref "R47") (pin "2") (pinfunction "2_2") (pintype "passive"))
    )
    (net (code "108") (name "PUSH") (class "Default")
      (node (ref "D20") (pin "A") (pinfunction "A_A") (pintype "passive"))
      (node (ref "IC5") (pin "8") (pinfunction "PUSH_8") (pintype "output"))
      (node (ref "R46") (pin "2") (pinfunction "2_2") (pintype "passive"))
    )
    (net (code "109") (name "REF") (class "Default")
      (node (ref "C37") (pin "2") (pinfunction "2_2") (pintype "passive"))
      (node (ref "IC4") (pin "3") (pinfunction "VDDI_3") (pintype "power_in"))
      (node (ref "IC4") (pin "8") (pinfunction "VDDI_8") (pintype "power_in"))
      (node (ref "R35") (pin "2") (pinfunction "2_2") (pintype "passive"))
      (node (ref "ZD4") (pin "C") (pinfunction "C_C") (pintype "passive"))
    )
    (net (code "110") (name "S1_DOT_OUT") (class "Default")
      (node (ref "IC6") (pin "4") (pinfunction "VD1_4") (pintype "passive"))
      (node (ref "Q7") (pin "3") (pinfunction "D_3") (pintype "passive"))
      (node (ref "R56") (pin "1") (pinfunction "1_1") (pintype "passive"))
      (node (ref "R57") (pin "1") (pinfunction "1_1") (pintype "passive"))
      (node (ref "TR3") (pin "S1_DOT") (pinfunction "S1_DOT_S1_DOT") (pintype "passive"))
    )
    (net (code "111") (name "S1_OUT") (class "Default")
      (node (ref "SH2") (pin "P$1") (pinfunction "GND_A_P$1") (pintype "bidirectional"))
      (node (ref "TR3") (pin "S1") (pinfunction "S1_S1") (pintype "passive"))
    )
    (net (code "112") (name "S2_DOT_OUT") (class "Default")
      (node (ref "SH3") (pin "P$2") (pinfunction "GND_B_P$2") (pintype "bidirectional"))
      (node (ref "TR3") (pin "S2_DOT") (pinfunction "S2_DOT_S2_DOT") (pintype "passive"))
    )
    (net (code "113") (name "S2_OUT") (class "Default")
      (node (ref "IC6") (pin "5") (pinfunction "VD2_5") (pintype "passive"))
      (node (ref "Q8") (pin "3") (pinfunction "D_3") (pintype "passive"))
      (node (ref "R62") (pin "1") (pinfunction "1_1") (pintype "passive"))
      (node (ref "R63") (pin "1") (pinfunction "1_1") (pintype "passive"))
      (node (ref "TR3") (pin "S2") (pinfunction "S2_S2") (pintype "passive"))
    )
    (net (code "114") (name "SR_OUT1") (class "Default")
      (node (ref "D22") (pin "A") (pinfunction "A_A") (pintype "passive"))
      (node (ref "Q7") (pin "1") (pinfunction "G_1") (pintype "passive"))
      (node (ref "R58") (pin "1") (pinfunction "1_1") (pintype "passive"))
    )
    (net (code "115") (name "SR_OUT2") (class "Default")
      (node (ref "D23") (pin "A") (pinfunction "A_A") (pintype "passive"))
      (node (ref "Q8") (pin "1") (pinfunction "G_1") (pintype "passive"))
      (node (ref "R61") (pin "1") (pinfunction "1_1") (pintype "passive"))
    )
    (net (code "116") (name "U_MON") (class "Default")
      (node (ref "JP4") (pin "NC") (pinfunction "NC_NC") (pintype "passive"))
      (node (ref "X3") (pin "1") (pinfunction "S_1") (pintype "passive"))
    )
    (net (code "117") (name "V+") (class "Default")
      (node (ref "C23") (pin "+") (pinfunction "+_+") (pintype "passive"))
      (node (ref "C64") (pin "1") (pinfunction "1_1") (pintype "passive"))
      (node (ref "C67") (pin "1") (pinfunction "1_1") (pintype "passive"))
      (node (ref "D7") (pin "A") (pinfunction "A_A") (pintype "passive"))
      (node (ref "D9") (pin "C") (pinfunction "C_C") (pintype "passive"))
      (node (ref "IC2") (pin "1") (pinfunction "OUT_1") (pintype "output"))
      (node (ref "IC7") (pin "8") (pinfunction "V+_8") (pintype "power_in"))
      (node (ref "IC8") (pin "8") (pinfunction "VCC+_8") (pintype "power_in"))
      (node (ref "R12") (pin "1") (pinfunction "1_1") (pintype "passive"))
      (node (ref "R16") (pin "1") (pinfunction "1_1") (pintype "passive"))
      (node (ref "R70") (pin "2") (pinfunction "2_2") (pintype "passive"))
      (node (ref "R72") (pin "2") (pinfunction "2_2") (pintype "passive"))
      (node (ref "X3") (pin "5") (pinfunction "S_5") (pintype "passive"))
    )
    (net (code "118") (name "V-") (class "Default")
      (node (ref "C17") (pin "2") (pinfunction "2_2") (pintype "passive"))
      (node (ref "C66") (pin "1") (pinfunction "1_1") (pintype "passive"))
      (node (ref "D3") (pin "A") (pinfunction "A_A") (pintype "passive"))
      (node (ref "D6") (pin "C") (pinfunction "C_C") (pintype "passive"))
      (node (ref "IC1") (pin "1") (pinfunction "OUT_1") (pintype "passive"))
      (node (ref "IC7") (pin "4") (pinfunction "V-_4") (pintype "power_in"))
      (node (ref "X3") (pin "7") (pinfunction "S_7") (pintype "passive"))
    )
    (net (code "119") (name "unconnected-(IC2-SD-Pad3)") (class "Default")
      (node (ref "IC2") (pin "3") (pinfunction "SD_3") (pintype "input"))
    )
    (net (code "120") (name "unconnected-(IC2-SENSE-Pad2)") (class "Default")
      (node (ref "IC2") (pin "2") (pinfunction "SENSE_2") (pintype "input"))
    )
    (net (code "121") (name "unconnected-(IC2-VTAP-Pad6)") (class "Default")
      (node (ref "IC2") (pin "6") (pinfunction "VTAP_6") (pintype "input"))
    )
  )
)
